# aqc-rev1.net
KiCad netlist of a schematic drawn in EAGLE
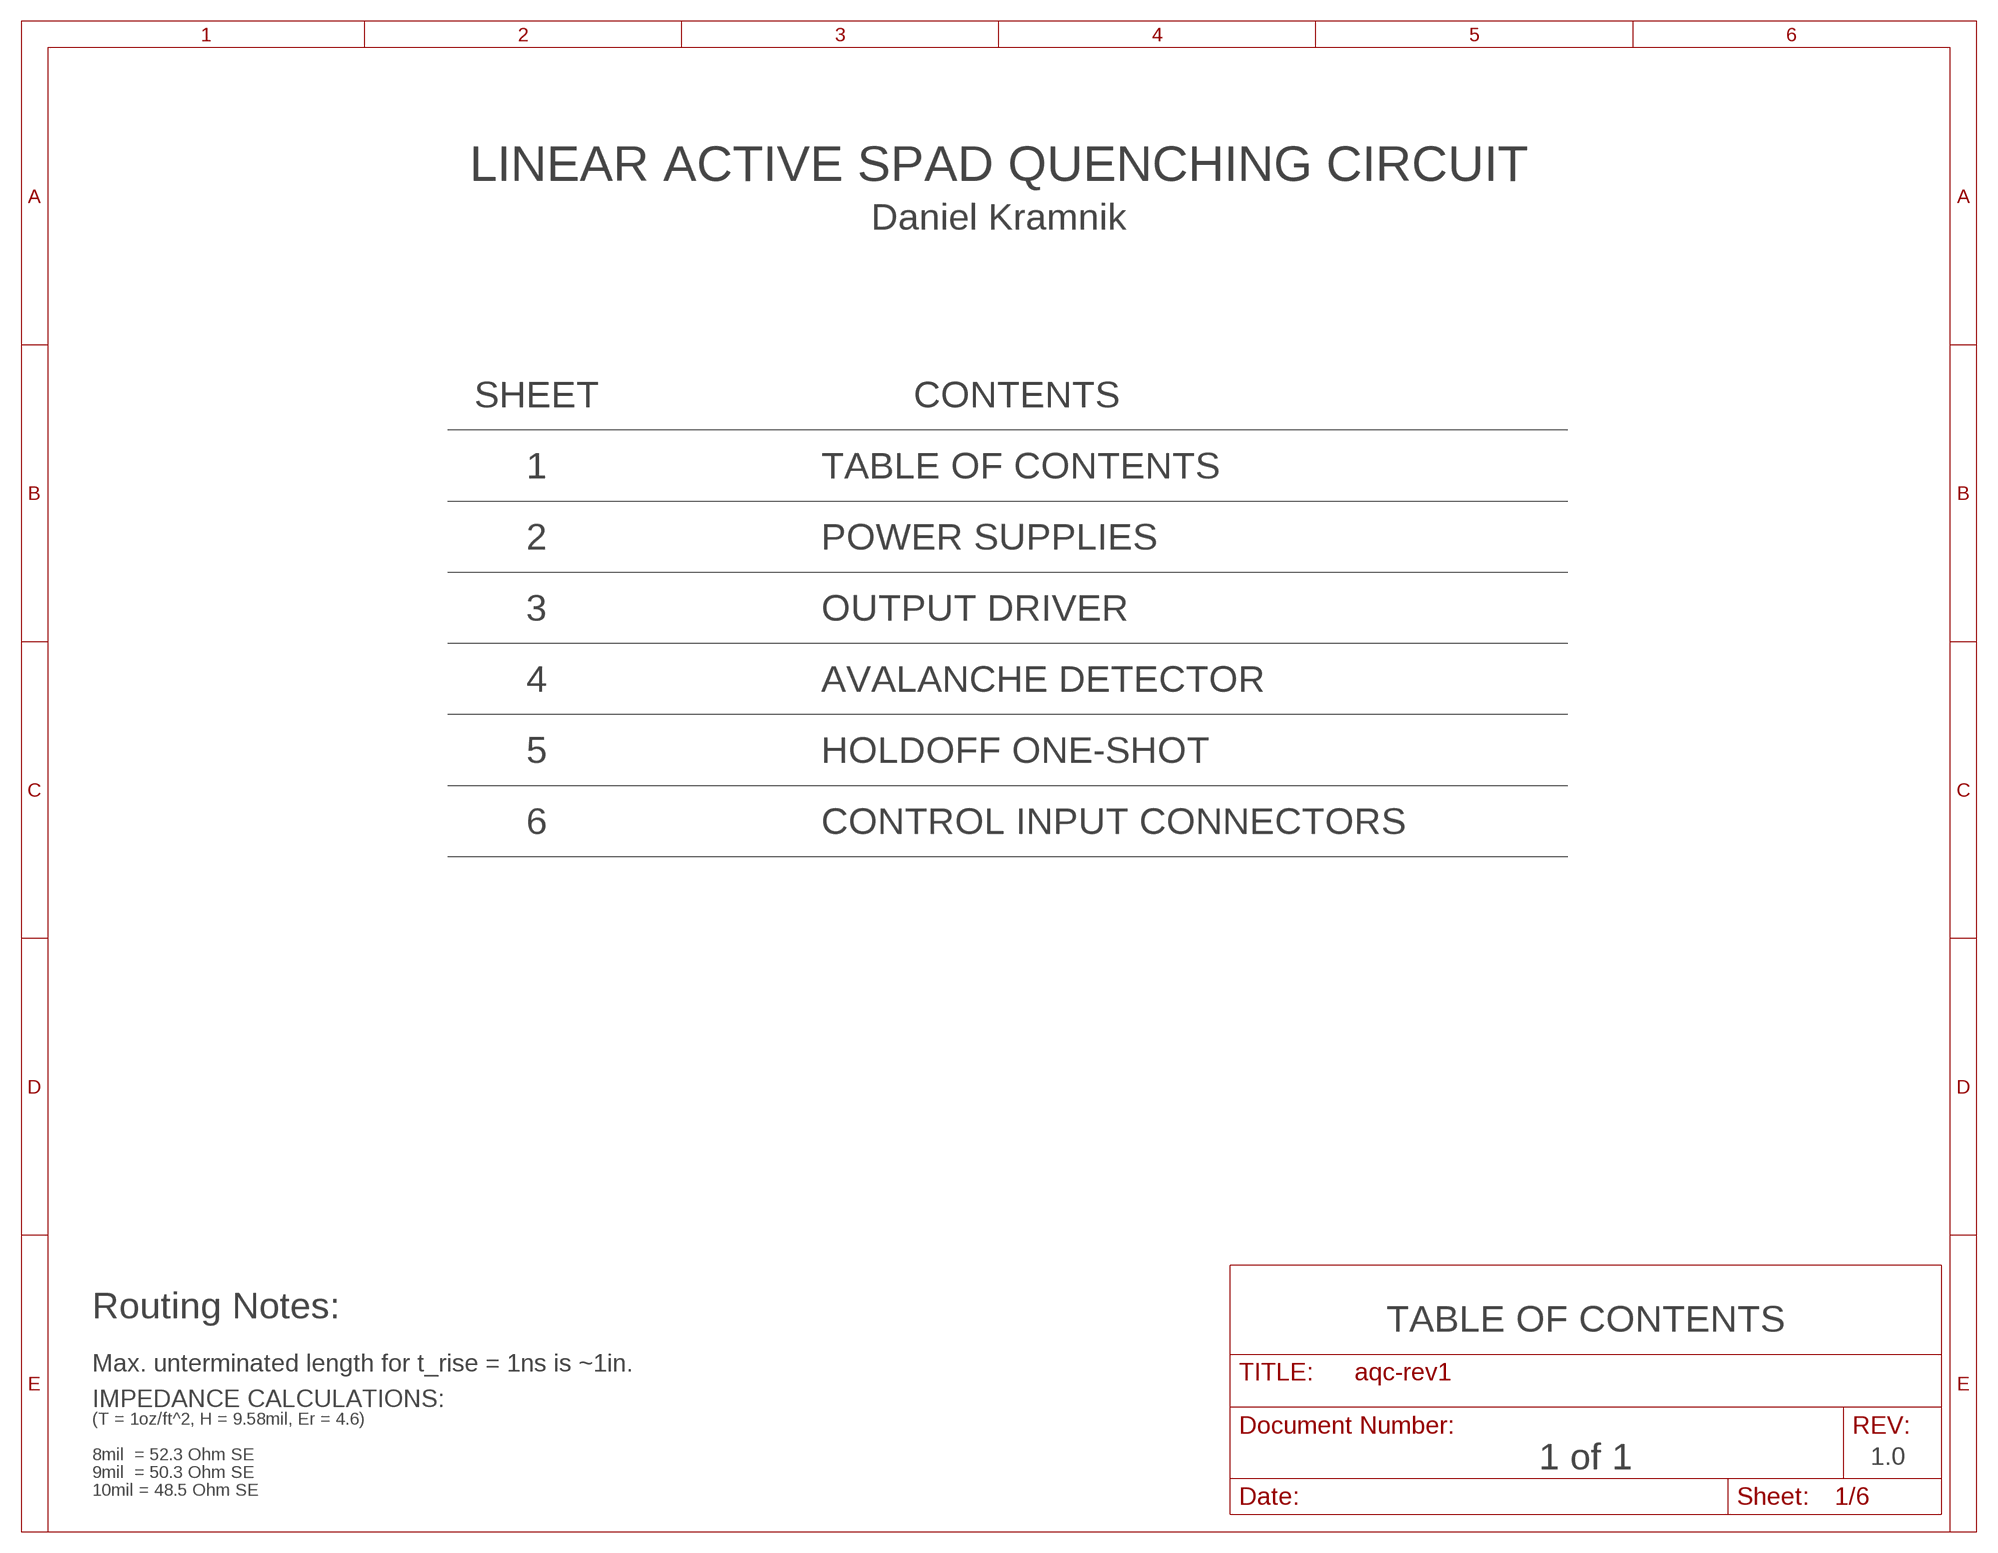
[diagram p0: schematic, sheet 1]
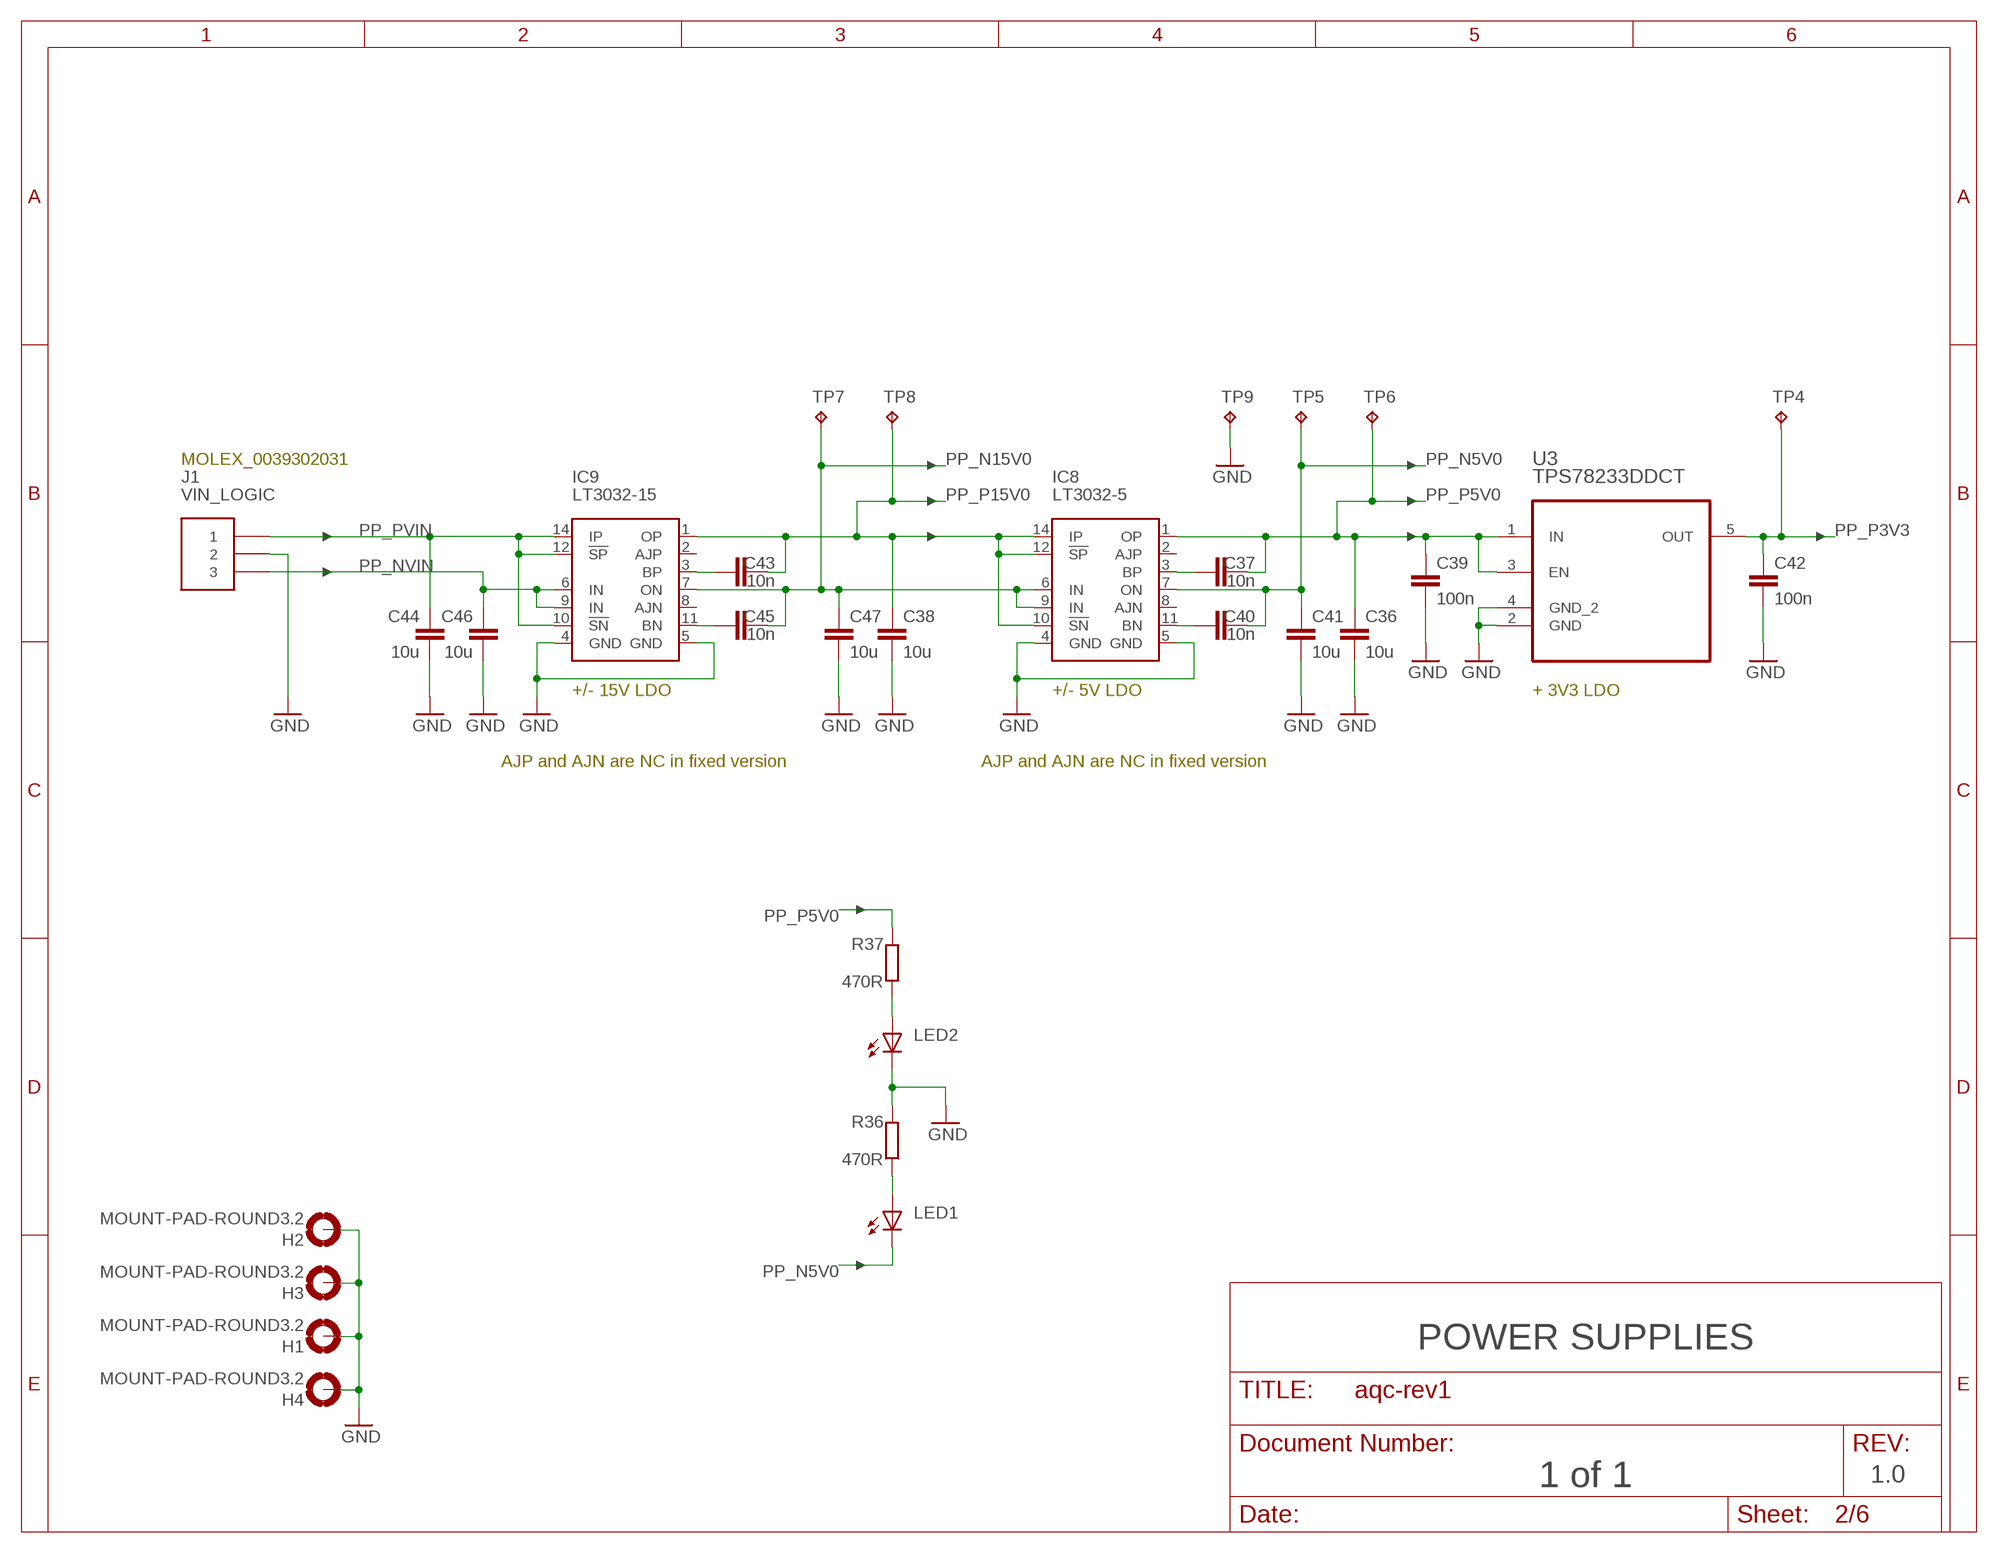
[diagram p1: schematic, sheet 2]
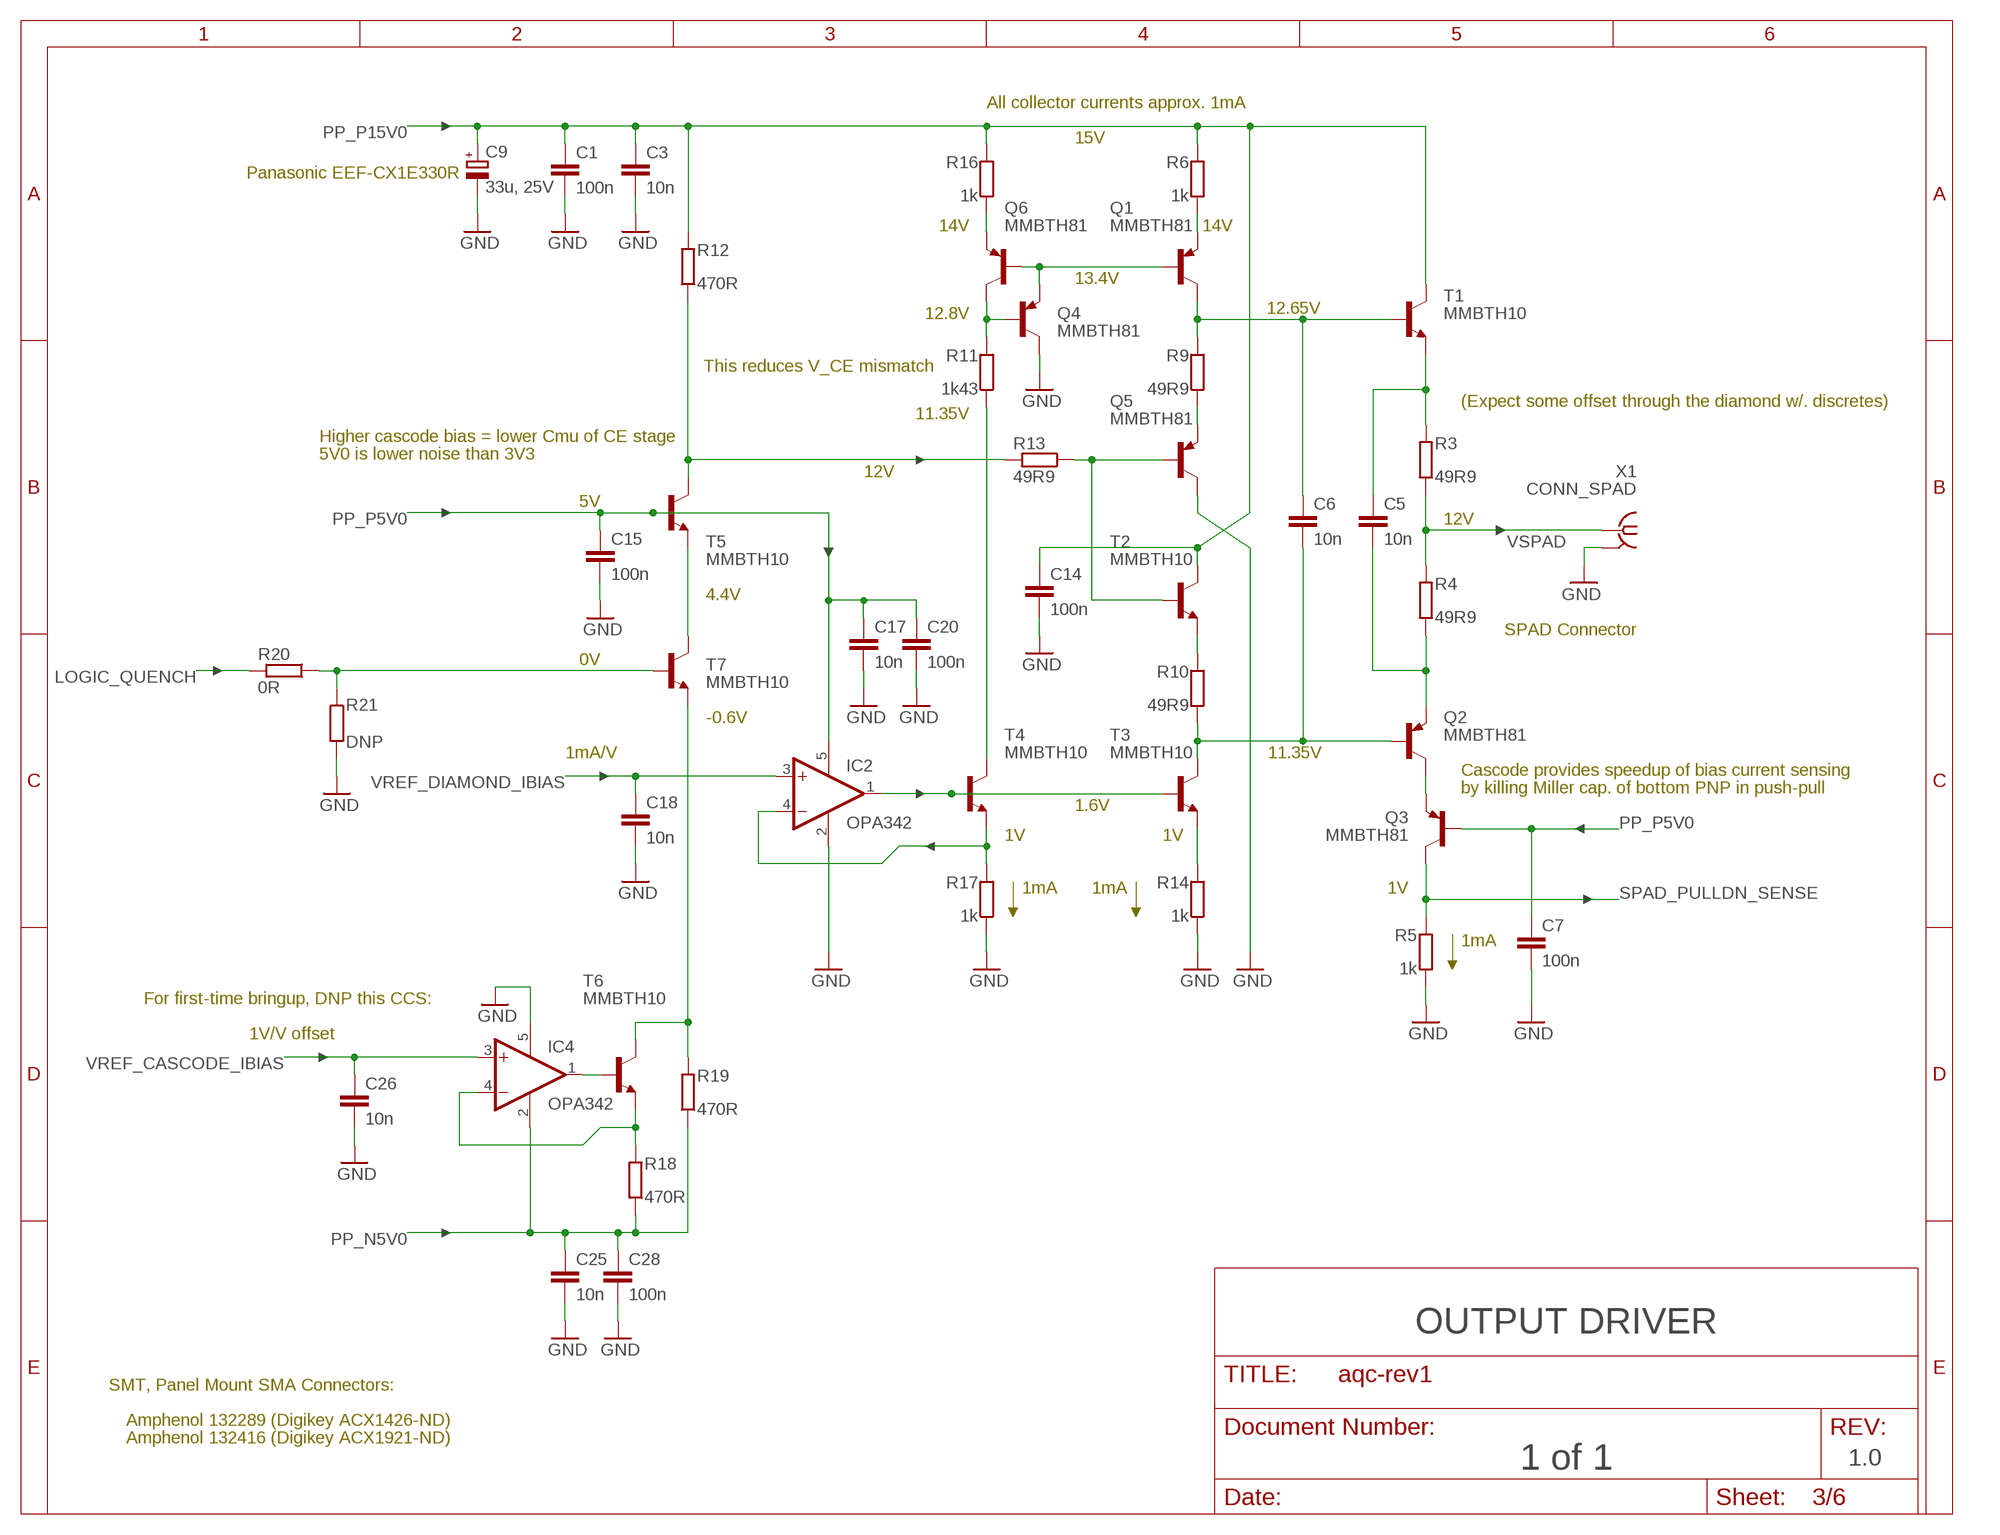
[diagram p2: schematic, sheet 3]
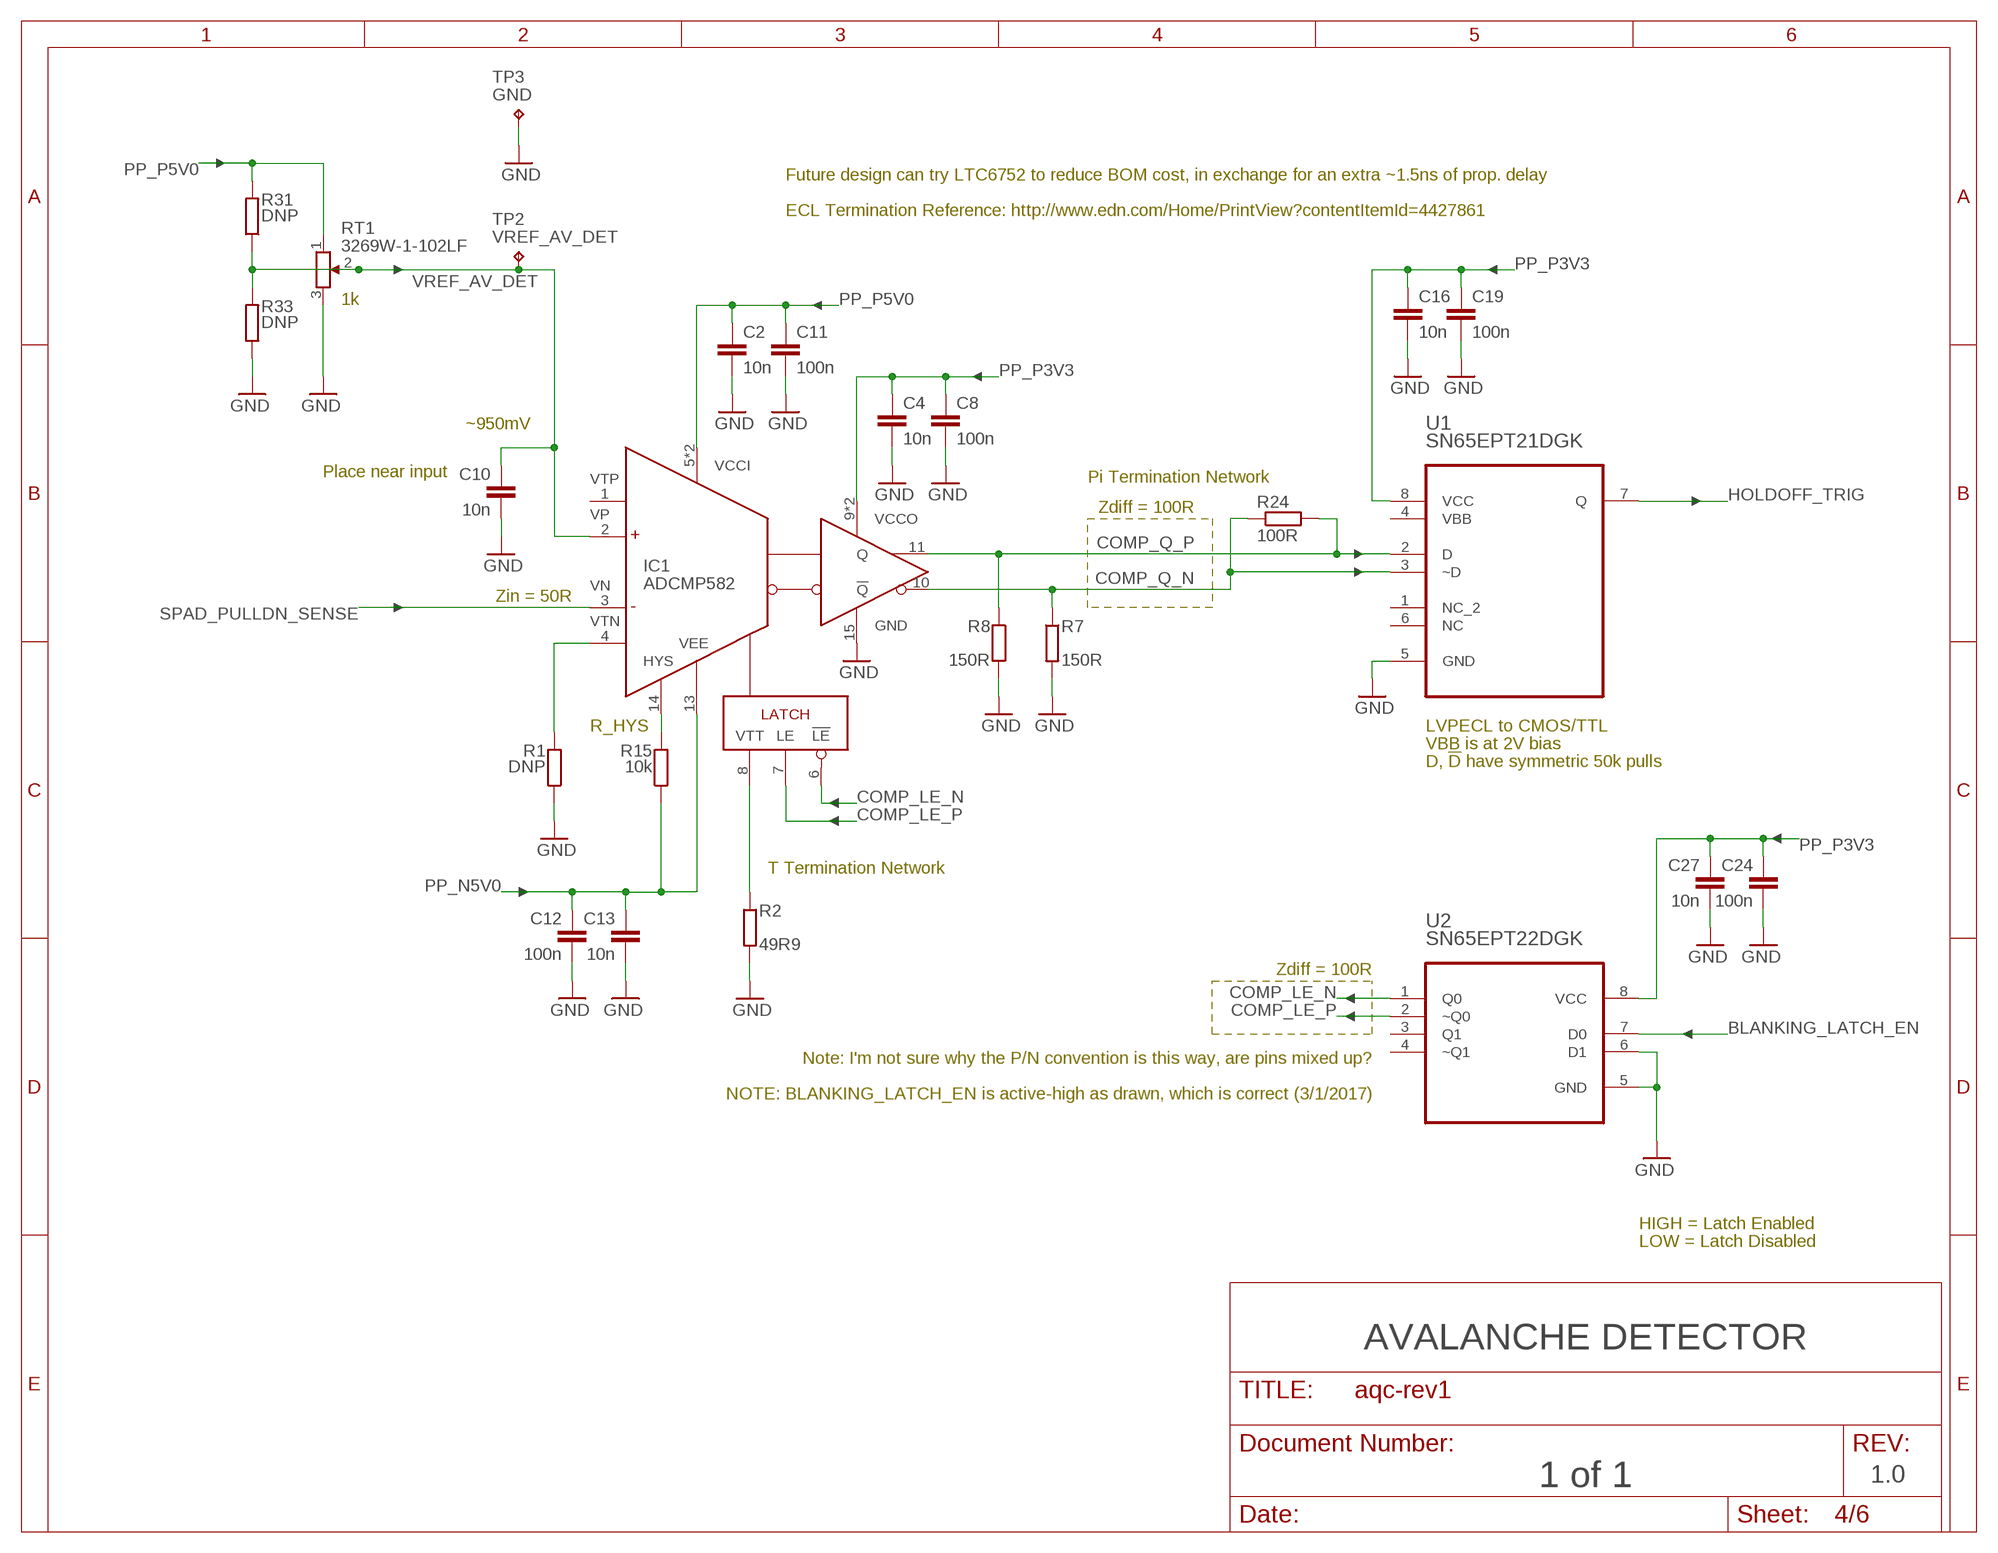
[diagram p3: schematic, sheet 4]
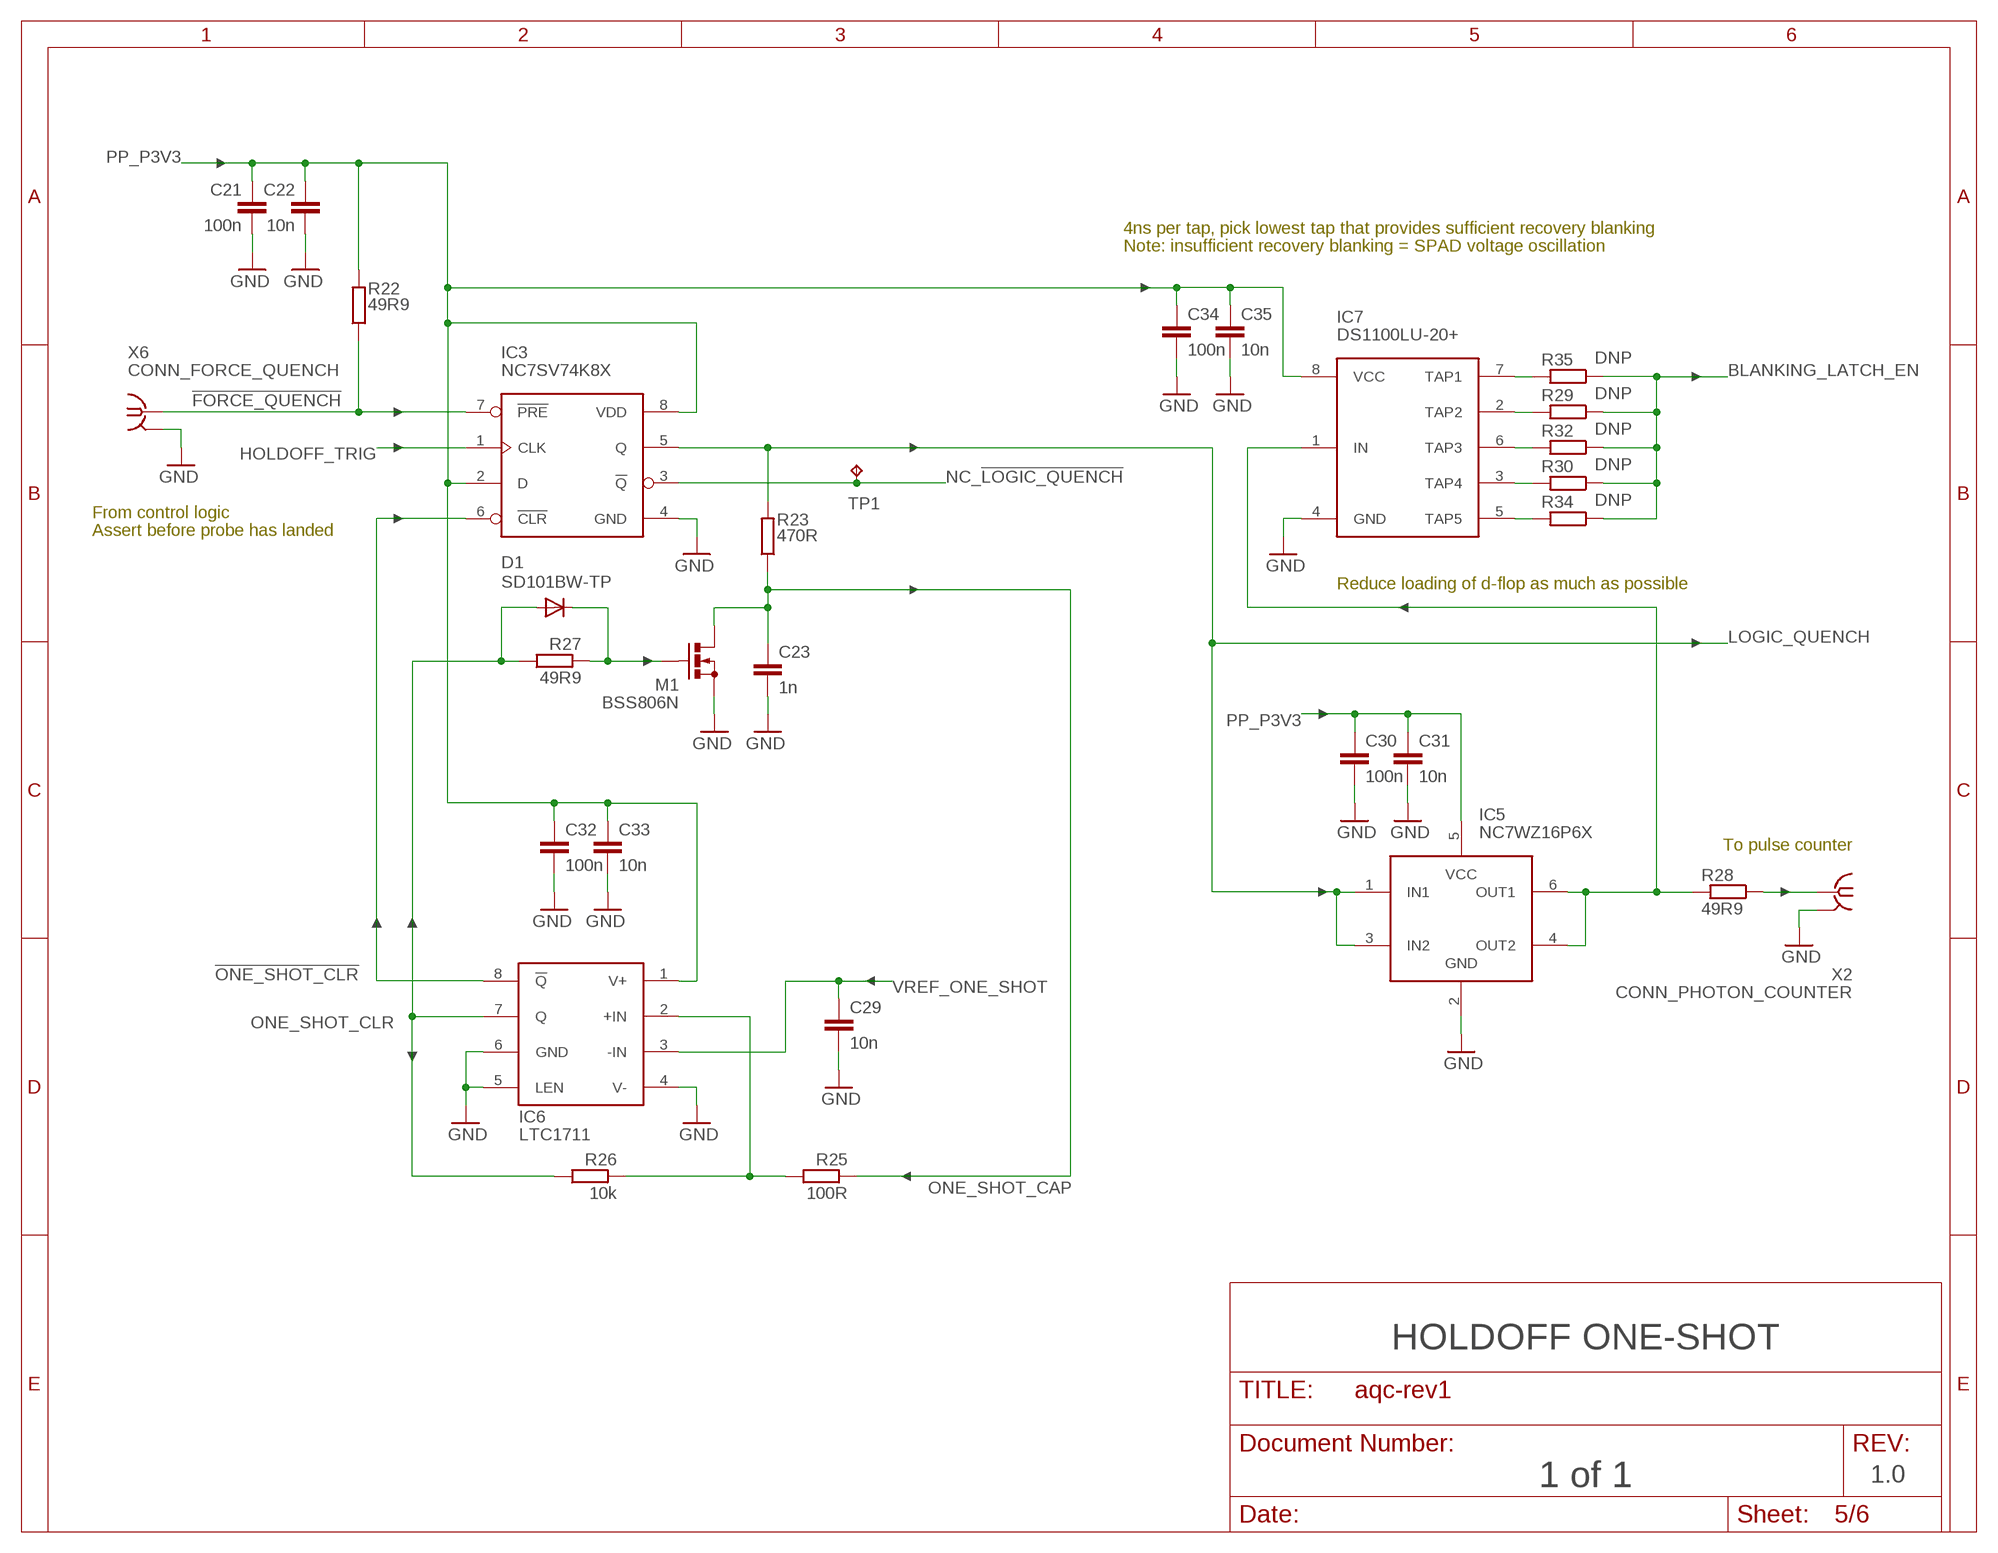
[diagram p4: schematic, sheet 5]
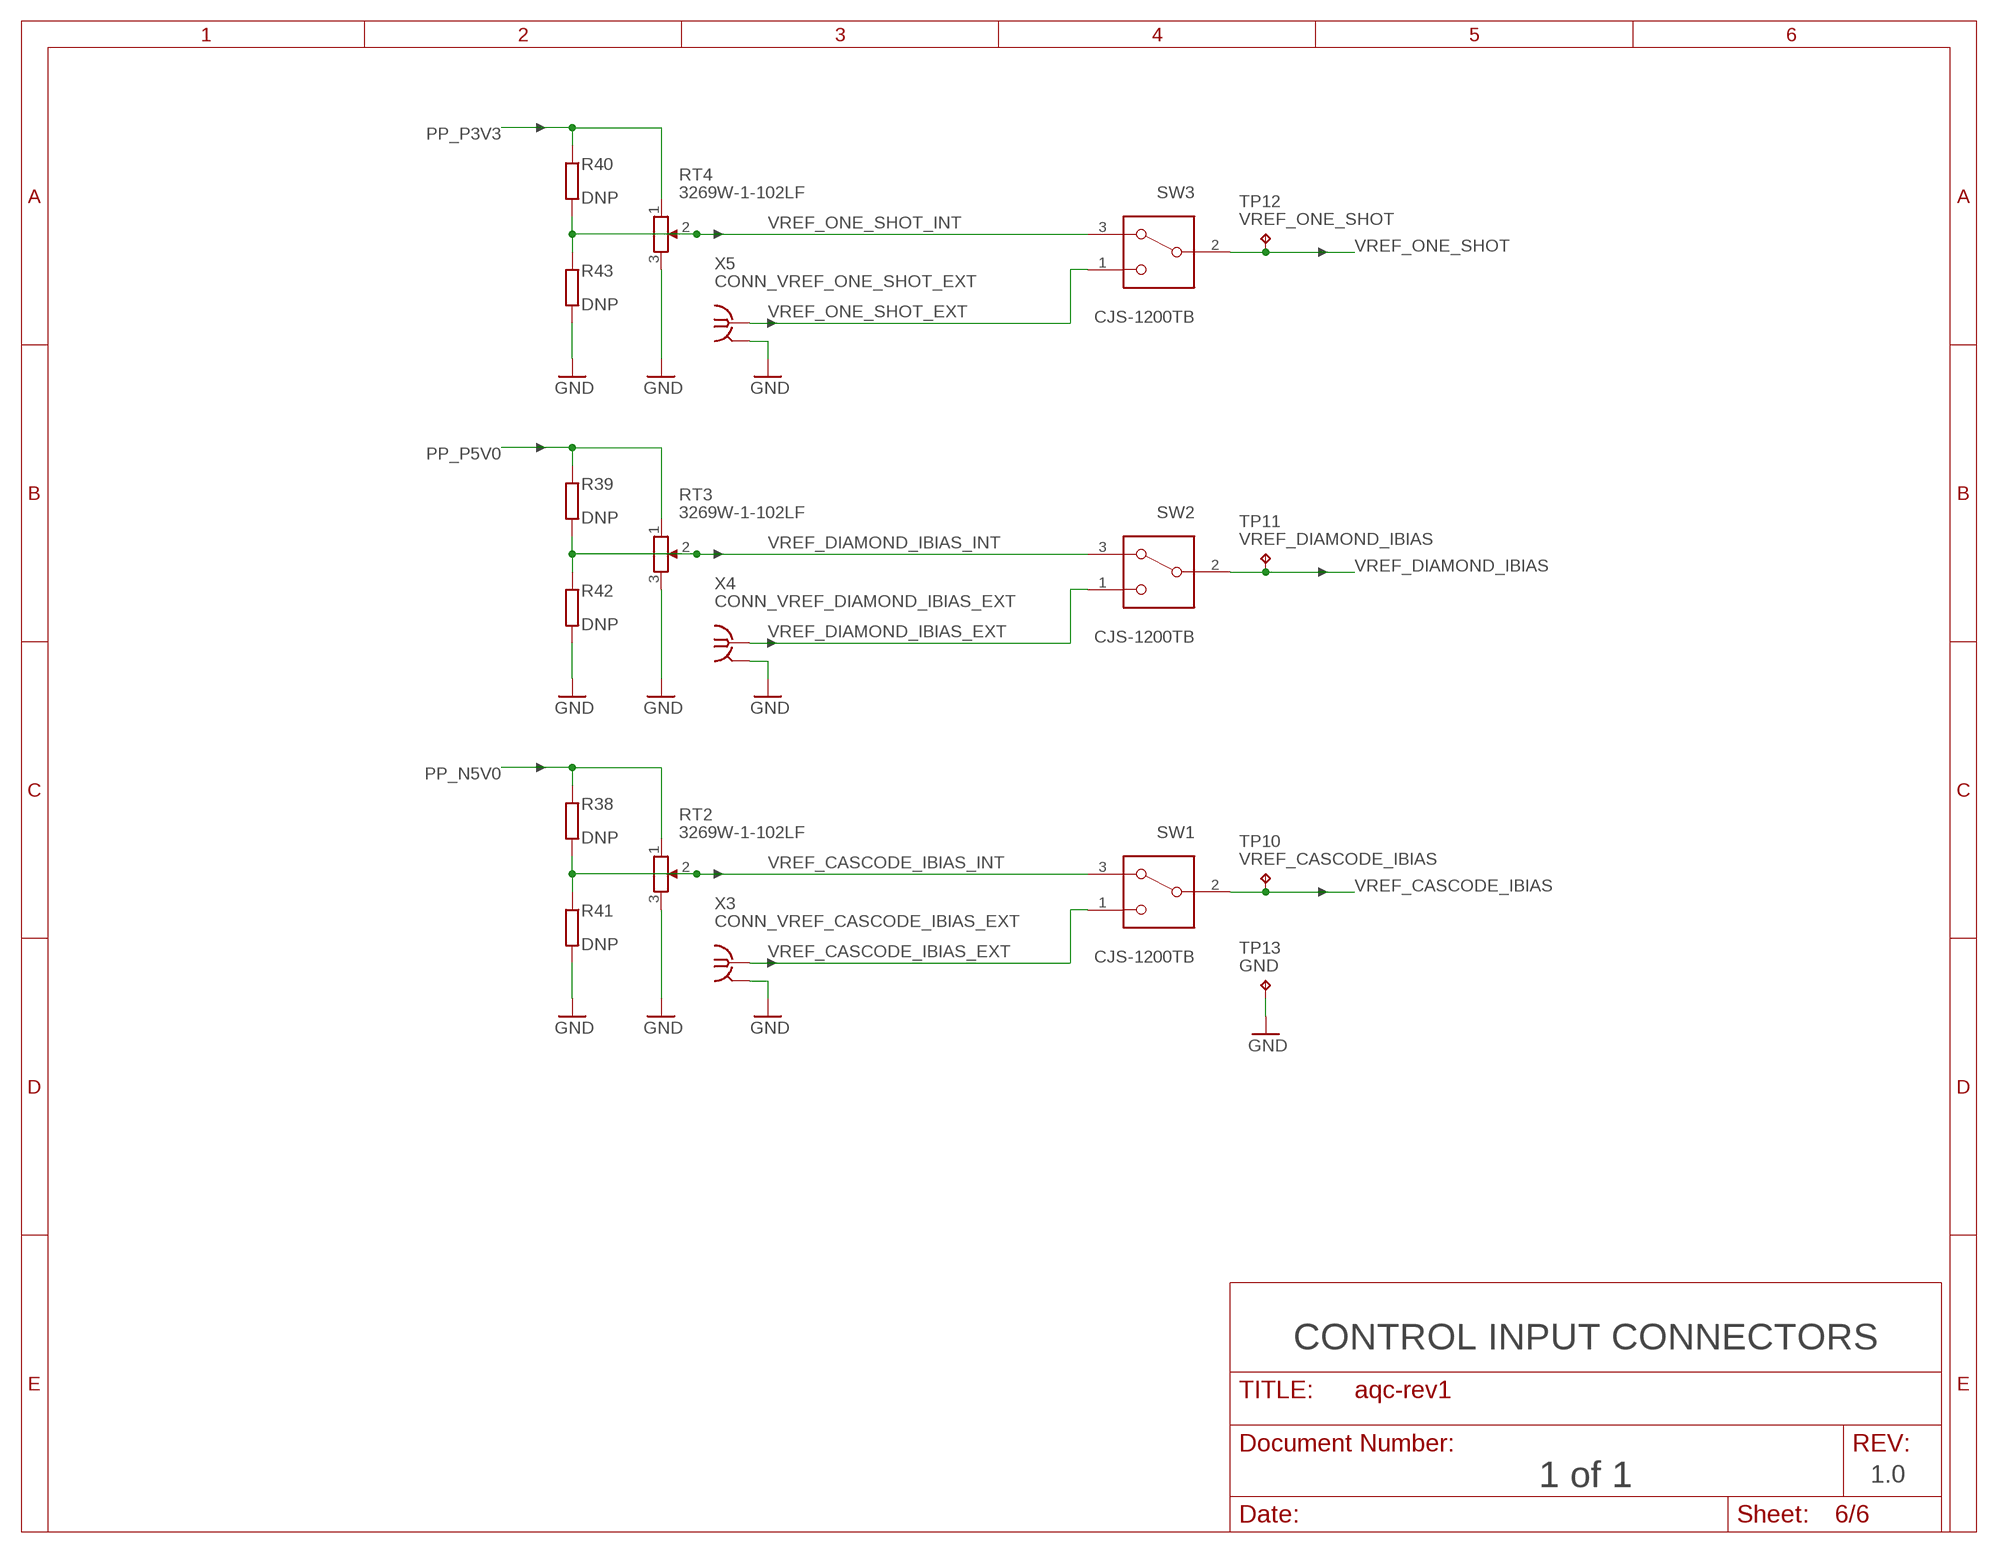
[diagram p5: schematic, sheet 6]

(export (version "E")
  (design (tool "Eeschema 10.0.6"))
  (components
    (comp (ref "C2")
      (value "10n")
      (footprint "eagle-import:C0402")
      (libsource (lib "eagle-import") (part "C-EUC0402"))
    )
    (comp (ref "C4")
      (value "10n")
      (footprint "eagle-import:C0402")
      (libsource (lib "eagle-import") (part "C-EUC0402"))
    )
    (comp (ref "C8")
      (value "100n")
      (footprint "eagle-import:C0402")
      (libsource (lib "eagle-import") (part "C-EUC0402"))
    )
    (comp (ref "C10")
      (value "10n")
      (footprint "eagle-import:C0603")
      (libsource (lib "eagle-import") (part "C-EUC0603"))
    )
    (comp (ref "C11")
      (value "100n")
      (footprint "eagle-import:C0402")
      (libsource (lib "eagle-import") (part "C-EUC0402"))
    )
    (comp (ref "C12")
      (value "100n")
      (footprint "eagle-import:C0402")
      (libsource (lib "eagle-import") (part "C-EUC0402"))
    )
    (comp (ref "C13")
      (value "10n")
      (footprint "eagle-import:C0402")
      (libsource (lib "eagle-import") (part "C-EUC0402"))
    )
    (comp (ref "C16")
      (value "10n")
      (footprint "eagle-import:C0402")
      (libsource (lib "eagle-import") (part "C-EUC0402"))
    )
    (comp (ref "C19")
      (value "100n")
      (footprint "eagle-import:C0402")
      (libsource (lib "eagle-import") (part "C-EUC0402"))
    )
    (comp (ref "C24")
      (value "100n")
      (footprint "eagle-import:C0402")
      (libsource (lib "eagle-import") (part "C-EUC0402"))
    )
    (comp (ref "C27")
      (value "10n")
      (footprint "eagle-import:C0402")
      (libsource (lib "eagle-import") (part "C-EUC0402"))
    )
    (comp (ref "IC1")
      (value "ADCMP582")
      (footprint "eagle-import:QFN50P300X300X80-16N")
      (libsource (lib "eagle-import") (part "ADCMP582"))
    )
    (comp (ref "R1")
      (value "DNP")
      (footprint "eagle-import:R0603")
      (libsource (lib "eagle-import") (part "R-EU_R0603"))
    )
    (comp (ref "R2")
      (value "49R9")
      (footprint "eagle-import:R0603")
      (libsource (lib "eagle-import") (part "R-EU_R0603"))
    )
    (comp (ref "R7")
      (value "150R")
      (footprint "eagle-import:R0402")
      (libsource (lib "eagle-import") (part "R-EU_R0402"))
    )
    (comp (ref "R8")
      (value "150R")
      (footprint "eagle-import:R0402")
      (libsource (lib "eagle-import") (part "R-EU_R0402"))
    )
    (comp (ref "R15")
      (value "10k")
      (footprint "eagle-import:R0603")
      (libsource (lib "eagle-import") (part "R-EU_R0603"))
    )
    (comp (ref "R24")
      (value "100R")
      (footprint "eagle-import:R0402")
      (libsource (lib "eagle-import") (part "R-EU_R0402"))
    )
    (comp (ref "R31")
      (value "DNP")
      (footprint "eagle-import:R0603")
      (libsource (lib "eagle-import") (part "R-EU_R0603"))
    )
    (comp (ref "R33")
      (value "DNP")
      (footprint "eagle-import:R0603")
      (libsource (lib "eagle-import") (part "R-EU_R0603"))
    )
    (comp (ref "RT1")
      (value "3269W-1-102LF")
      (footprint "eagle-import:3269W")
      (libsource (lib "eagle-import") (part "BOURNS_3269WX"))
    )
    (comp (ref "TP2")
      (value "VREF_AV_DET")
      (footprint "eagle-import:KEYSTONE_5000_MINIATURE")
      (libsource (lib "eagle-import") (part "KEYSTONE_5000"))
    )
    (comp (ref "TP3")
      (value "GND")
      (footprint "eagle-import:KEYSTONE_5000_MINIATURE")
      (libsource (lib "eagle-import") (part "KEYSTONE_5000"))
    )
    (comp (ref "U1")
      (value "SN65EPT21DGK")
      (footprint "eagle-import:SOP65P490X110-8N")
      (libsource (lib "eagle-import") (part "SN65EPT21DGK"))
    )
    (comp (ref "U2")
      (value "SN65EPT22DGK")
      (footprint "eagle-import:SOP65P490X110-8N")
      (libsource (lib "eagle-import") (part "SN65EPT22DGK"))
    )
    (comp (ref "C36")
      (value "10u")
      (footprint "eagle-import:C1206")
      (libsource (lib "eagle-import") (part "C-EUC1206"))
    )
    (comp (ref "C37")
      (value "10n")
      (footprint "eagle-import:C0603")
      (libsource (lib "eagle-import") (part "C-EUC0603"))
    )
    (comp (ref "C38")
      (value "10u")
      (footprint "eagle-import:C1206")
      (libsource (lib "eagle-import") (part "C-EUC1206"))
    )
    (comp (ref "C39")
      (value "100n")
      (footprint "eagle-import:C0603")
      (libsource (lib "eagle-import") (part "C-EUC0603"))
    )
    (comp (ref "C40")
      (value "10n")
      (footprint "eagle-import:C0603")
      (libsource (lib "eagle-import") (part "C-EUC0603"))
    )
    (comp (ref "C41")
      (value "10u")
      (footprint "eagle-import:C1206")
      (libsource (lib "eagle-import") (part "C-EUC1206"))
    )
    (comp (ref "C42")
      (value "100n")
      (footprint "eagle-import:C0603")
      (libsource (lib "eagle-import") (part "C-EUC0603"))
    )
    (comp (ref "C43")
      (value "10n")
      (footprint "eagle-import:C0603")
      (libsource (lib "eagle-import") (part "C-EUC0603"))
    )
    (comp (ref "C44")
      (value "10u")
      (footprint "eagle-import:C1206")
      (libsource (lib "eagle-import") (part "C-EUC1206"))
    )
    (comp (ref "C45")
      (value "10n")
      (footprint "eagle-import:C0603")
      (libsource (lib "eagle-import") (part "C-EUC0603"))
    )
    (comp (ref "C46")
      (value "10u")
      (footprint "eagle-import:C1206")
      (libsource (lib "eagle-import") (part "C-EUC1206"))
    )
    (comp (ref "C47")
      (value "10u")
      (footprint "eagle-import:C1206")
      (libsource (lib "eagle-import") (part "C-EUC1206"))
    )
    (comp (ref "H1")
      (value "MOUNT-PAD-ROUND3.2")
      (footprint "eagle-import:3,2-PAD")
      (libsource (lib "eagle-import") (part "MOUNT-PAD-ROUND3.2"))
    )
    (comp (ref "H2")
      (value "MOUNT-PAD-ROUND3.2")
      (footprint "eagle-import:3,2-PAD")
      (libsource (lib "eagle-import") (part "MOUNT-PAD-ROUND3.2"))
    )
    (comp (ref "H3")
      (value "MOUNT-PAD-ROUND3.2")
      (footprint "eagle-import:3,2-PAD")
      (libsource (lib "eagle-import") (part "MOUNT-PAD-ROUND3.2"))
    )
    (comp (ref "H4")
      (value "MOUNT-PAD-ROUND3.2")
      (footprint "eagle-import:3,2-PAD")
      (libsource (lib "eagle-import") (part "MOUNT-PAD-ROUND3.2"))
    )
    (comp (ref "IC8")
      (value "LT3032-5")
      (footprint "eagle-import:DFN14-4X3DE")
      (libsource (lib "eagle-import") (part "LT3032"))
    )
    (comp (ref "IC9")
      (value "LT3032-15")
      (footprint "eagle-import:DFN14-4X3DE")
      (libsource (lib "eagle-import") (part "LT3032"))
    )
    (comp (ref "J1")
      (value "VIN_LOGIC")
      (footprint "eagle-import:CONN_MOLEX_3PIN_MINI-FIT_JR")
      (libsource (lib "eagle-import") (part "CONN_MOLEX_3PIN_MINI-FIT_JR"))
    )
    (comp (ref "LED1")
      (value "LEDCHIP-LED0805")
      (footprint "eagle-import:CHIP-LED0805")
      (libsource (lib "eagle-import") (part "LEDCHIP-LED0805"))
    )
    (comp (ref "LED2")
      (value "LEDCHIP-LED0805")
      (footprint "eagle-import:CHIP-LED0805")
      (libsource (lib "eagle-import") (part "LEDCHIP-LED0805"))
    )
    (comp (ref "R36")
      (value "470R")
      (footprint "eagle-import:R0805")
      (libsource (lib "eagle-import") (part "resistor_R-EU_R0805"))
    )
    (comp (ref "R37")
      (value "470R")
      (footprint "eagle-import:R0805")
      (libsource (lib "eagle-import") (part "resistor_R-EU_R0805"))
    )
    (comp (ref "TP4")
      (value "TPTP20R")
      (footprint "eagle-import:TP20R")
      (libsource (lib "eagle-import") (part "TPTP20R"))
    )
    (comp (ref "TP5")
      (value "TPTP20R")
      (footprint "eagle-import:TP20R")
      (libsource (lib "eagle-import") (part "TPTP20R"))
    )
    (comp (ref "TP6")
      (value "TPTP20R")
      (footprint "eagle-import:TP20R")
      (libsource (lib "eagle-import") (part "TPTP20R"))
    )
    (comp (ref "TP7")
      (value "TPTP20R")
      (footprint "eagle-import:TP20R")
      (libsource (lib "eagle-import") (part "TPTP20R"))
    )
    (comp (ref "TP8")
      (value "TPTP20R")
      (footprint "eagle-import:TP20R")
      (libsource (lib "eagle-import") (part "TPTP20R"))
    )
    (comp (ref "TP9")
      (value "TPTP20R")
      (footprint "eagle-import:TP20R")
      (libsource (lib "eagle-import") (part "TPTP20R"))
    )
    (comp (ref "U3")
      (value "TPS78233DDCT")
      (footprint "eagle-import:SOT95P280X110-5N")
      (libsource (lib "eagle-import") (part "TPS78233DDCT"))
    )
    (comp (ref "C1")
      (value "100n")
      (footprint "eagle-import:C0603")
      (libsource (lib "eagle-import") (part "C-EUC0603"))
    )
    (comp (ref "C3")
      (value "10n")
      (footprint "eagle-import:C0603")
      (libsource (lib "eagle-import") (part "C-EUC0603"))
    )
    (comp (ref "C5")
      (value "10n")
      (footprint "eagle-import:C0603")
      (libsource (lib "eagle-import") (part "C-EUC0603"))
    )
    (comp (ref "C6")
      (value "10n")
      (footprint "eagle-import:C0603")
      (libsource (lib "eagle-import") (part "C-EUC0603"))
    )
    (comp (ref "C7")
      (value "100n")
      (footprint "eagle-import:C0603")
      (libsource (lib "eagle-import") (part "C-EUC0603"))
    )
    (comp (ref "C9")
      (value "33u, 25V")
      (footprint "eagle-import:CT7343")
      (libsource (lib "eagle-import") (part "CPOL-EUCT7343"))
    )
    (comp (ref "C14")
      (value "100n")
      (footprint "eagle-import:C0603")
      (libsource (lib "eagle-import") (part "C-EUC0603"))
    )
    (comp (ref "C15")
      (value "100n")
      (footprint "eagle-import:C0603")
      (libsource (lib "eagle-import") (part "C-EUC0603"))
    )
    (comp (ref "C17")
      (value "10n")
      (footprint "eagle-import:C0402")
      (libsource (lib "eagle-import") (part "C-EUC0402"))
    )
    (comp (ref "C18")
      (value "10n")
      (footprint "eagle-import:C0402")
      (libsource (lib "eagle-import") (part "C-EUC0402"))
    )
    (comp (ref "C20")
      (value "100n")
      (footprint "eagle-import:C0402")
      (libsource (lib "eagle-import") (part "C-EUC0402"))
    )
    (comp (ref "C25")
      (value "10n")
      (footprint "eagle-import:C0402")
      (libsource (lib "eagle-import") (part "C-EUC0402"))
    )
    (comp (ref "C26")
      (value "10n")
      (footprint "eagle-import:C0402")
      (libsource (lib "eagle-import") (part "C-EUC0402"))
    )
    (comp (ref "C28")
      (value "100n")
      (footprint "eagle-import:C0402")
      (libsource (lib "eagle-import") (part "C-EUC0402"))
    )
    (comp (ref "IC2")
      (value "OPA342")
      (footprint "eagle-import:SOT23-5")
      (libsource (lib "eagle-import") (part "OPA333DBV"))
    )
    (comp (ref "IC4")
      (value "OPA342")
      (footprint "eagle-import:SOT23-5")
      (libsource (lib "eagle-import") (part "OPA333DBV"))
    )
    (comp (ref "Q1")
      (value "MMBTH81")
      (footprint "eagle-import:SOT23-BEC")
      (libsource (lib "eagle-import") (part "MMBTH81SMDLT1"))
    )
    (comp (ref "Q2")
      (value "MMBTH81")
      (footprint "eagle-import:SOT23-BEC")
      (libsource (lib "eagle-import") (part "MMBTH81SMDLT1"))
    )
    (comp (ref "Q3")
      (value "MMBTH81")
      (footprint "eagle-import:SOT23-BEC")
      (libsource (lib "eagle-import") (part "MMBTH81SMDLT1"))
    )
    (comp (ref "Q4")
      (value "MMBTH81")
      (footprint "eagle-import:SOT23-BEC")
      (libsource (lib "eagle-import") (part "MMBTH81SMDLT1"))
    )
    (comp (ref "Q5")
      (value "MMBTH81")
      (footprint "eagle-import:SOT23-BEC")
      (libsource (lib "eagle-import") (part "MMBTH81SMDLT1"))
    )
    (comp (ref "Q6")
      (value "MMBTH81")
      (footprint "eagle-import:SOT23-BEC")
      (libsource (lib "eagle-import") (part "MMBTH81SMDLT1"))
    )
    (comp (ref "R3")
      (value "49R9")
      (footprint "eagle-import:R0603")
      (libsource (lib "eagle-import") (part "R-EU_R0603"))
    )
    (comp (ref "R4")
      (value "49R9")
      (footprint "eagle-import:R0603")
      (libsource (lib "eagle-import") (part "R-EU_R0603"))
    )
    (comp (ref "R5")
      (value "1k")
      (footprint "eagle-import:R0603")
      (libsource (lib "eagle-import") (part "R-EU_R0603"))
    )
    (comp (ref "R6")
      (value "1k")
      (footprint "eagle-import:R0603")
      (libsource (lib "eagle-import") (part "R-EU_R0603"))
    )
    (comp (ref "R9")
      (value "49R9")
      (footprint "eagle-import:R0603")
      (libsource (lib "eagle-import") (part "R-EU_R0603"))
    )
    (comp (ref "R10")
      (value "49R9")
      (footprint "eagle-import:R0603")
      (libsource (lib "eagle-import") (part "R-EU_R0603"))
    )
    (comp (ref "R11")
      (value "1k43")
      (footprint "eagle-import:R0603")
      (libsource (lib "eagle-import") (part "R-EU_R0603"))
    )
    (comp (ref "R12")
      (value "470R")
      (footprint "eagle-import:R0603")
      (libsource (lib "eagle-import") (part "R-EU_R0603"))
    )
    (comp (ref "R13")
      (value "49R9")
      (footprint "eagle-import:R0603")
      (libsource (lib "eagle-import") (part "R-EU_R0603"))
    )
    (comp (ref "R14")
      (value "1k")
      (footprint "eagle-import:R0603")
      (libsource (lib "eagle-import") (part "R-EU_R0603"))
    )
    (comp (ref "R16")
      (value "1k")
      (footprint "eagle-import:R0603")
      (libsource (lib "eagle-import") (part "R-EU_R0603"))
    )
    (comp (ref "R17")
      (value "1k")
      (footprint "eagle-import:R0603")
      (libsource (lib "eagle-import") (part "R-EU_R0603"))
    )
    (comp (ref "R18")
      (value "470R")
      (footprint "eagle-import:R0603")
      (libsource (lib "eagle-import") (part "R-EU_R0603"))
    )
    (comp (ref "R19")
      (value "470R")
      (footprint "eagle-import:R0603")
      (libsource (lib "eagle-import") (part "R-EU_R0603"))
    )
    (comp (ref "R20")
      (value "0R")
      (footprint "eagle-import:R0603")
      (libsource (lib "eagle-import") (part "R-EU_R0603"))
    )
    (comp (ref "R21")
      (value "DNP")
      (footprint "eagle-import:R0603")
      (libsource (lib "eagle-import") (part "R-EU_R0603"))
    )
    (comp (ref "T1")
      (value "MMBTH10")
      (footprint "eagle-import:SOT23-BEC")
      (libsource (lib "eagle-import") (part "-NPN-SOT23-BECMMBTH10LT1"))
    )
    (comp (ref "T2")
      (value "MMBTH10")
      (footprint "eagle-import:SOT23-BEC")
      (libsource (lib "eagle-import") (part "-NPN-SOT23-BECMMBTH10LT1"))
    )
    (comp (ref "T3")
      (value "MMBTH10")
      (footprint "eagle-import:SOT23-BEC")
      (libsource (lib "eagle-import") (part "-NPN-SOT23-BECMMBTH10LT1"))
    )
    (comp (ref "T4")
      (value "MMBTH10")
      (footprint "eagle-import:SOT23-BEC")
      (libsource (lib "eagle-import") (part "-NPN-SOT23-BECMMBTH10LT1"))
    )
    (comp (ref "T5")
      (value "MMBTH10")
      (footprint "eagle-import:SOT23-BEC")
      (libsource (lib "eagle-import") (part "-NPN-SOT23-BECMMBTH10LT1"))
    )
    (comp (ref "T6")
      (value "MMBTH10")
      (footprint "eagle-import:SOT23-BEC")
      (libsource (lib "eagle-import") (part "-NPN-SOT23-BECMMBTH10LT1"))
    )
    (comp (ref "T7")
      (value "MMBTH10")
      (footprint "eagle-import:SOT23-BEC")
      (libsource (lib "eagle-import") (part "-NPN-SOT23-BECMMBTH10LT1"))
    )
    (comp (ref "X1")
      (value "CONN_SPAD")
      (footprint "eagle-import:J502-ND-142-0711-871_876")
      (fields (field (name "MF") "JOHNSON COMPONENTS") (field (name "MPN") "142-0711-871"))
      (libsource (lib "eagle-import") (part "SMA-142-0711-871/876"))
    )
    (comp (ref "C21")
      (value "100n")
      (footprint "eagle-import:C0402")
      (libsource (lib "eagle-import") (part "C-EUC0402"))
    )
    (comp (ref "C22")
      (value "10n")
      (footprint "eagle-import:C0402")
      (libsource (lib "eagle-import") (part "C-EUC0402"))
    )
    (comp (ref "C23")
      (value "1n")
      (footprint "eagle-import:C0603")
      (libsource (lib "eagle-import") (part "C-EUC0603"))
    )
    (comp (ref "C29")
      (value "10n")
      (footprint "eagle-import:C0402")
      (libsource (lib "eagle-import") (part "C-EUC0402"))
    )
    (comp (ref "C30")
      (value "100n")
      (footprint "eagle-import:C0402")
      (libsource (lib "eagle-import") (part "C-EUC0402"))
    )
    (comp (ref "C31")
      (value "10n")
      (footprint "eagle-import:C0402")
      (libsource (lib "eagle-import") (part "C-EUC0402"))
    )
    (comp (ref "C32")
      (value "100n")
      (footprint "eagle-import:C0402")
      (libsource (lib "eagle-import") (part "C-EUC0402"))
    )
    (comp (ref "C33")
      (value "10n")
      (footprint "eagle-import:C0402")
      (libsource (lib "eagle-import") (part "C-EUC0402"))
    )
    (comp (ref "C34")
      (value "100n")
      (footprint "eagle-import:C0402")
      (libsource (lib "eagle-import") (part "C-EUC0402"))
    )
    (comp (ref "C35")
      (value "10n")
      (footprint "eagle-import:C0402")
      (libsource (lib "eagle-import") (part "C-EUC0402"))
    )
    (comp (ref "D1")
      (value "SD101BW-TP")
      (footprint "eagle-import:SOD123")
      (libsource (lib "eagle-import") (part "DIODE-SOD123"))
    )
    (comp (ref "IC3")
      (value "NC7SV74K8X")
      (footprint "eagle-import:US8_3.1MM_JDEC_MO-187")
      (libsource (lib "eagle-import") (part "NC7SV74K8X"))
    )
    (comp (ref "IC5")
      (value "NC7WZ16P6X")
      (footprint "eagle-import:SC70-6L")
      (libsource (lib "eagle-import") (part "NC7WZ16P6X"))
    )
    (comp (ref "IC6")
      (value "LTC1711")
      (footprint "eagle-import:MSOP8")
      (libsource (lib "eagle-import") (part "LTC1711"))
    )
    (comp (ref "IC7")
      (value "DS1100LU-20+")
      (footprint "eagle-import:MSOP8")
      (libsource (lib "eagle-import") (part "DS1100L"))
    )
    (comp (ref "M1")
      (value "BSS806N")
      (footprint "eagle-import:SOT23R_INFINEON")
      (libsource (lib "eagle-import") (part "BSS806N"))
    )
    (comp (ref "R22")
      (value "49R9")
      (footprint "eagle-import:R0603")
      (libsource (lib "eagle-import") (part "R-EU_R0603"))
    )
    (comp (ref "R23")
      (value "470R")
      (footprint "eagle-import:R0603")
      (libsource (lib "eagle-import") (part "R-EU_R0603"))
    )
    (comp (ref "R25")
      (value "100R")
      (footprint "eagle-import:R0603")
      (libsource (lib "eagle-import") (part "R-EU_R0603"))
    )
    (comp (ref "R26")
      (value "10k")
      (footprint "eagle-import:R0603")
      (libsource (lib "eagle-import") (part "R-EU_R0603"))
    )
    (comp (ref "R27")
      (value "49R9")
      (footprint "eagle-import:R0603")
      (libsource (lib "eagle-import") (part "R-EU_R0603"))
    )
    (comp (ref "R28")
      (value "49R9")
      (footprint "eagle-import:R0603")
      (libsource (lib "eagle-import") (part "R-EU_R0603"))
    )
    (comp (ref "R29")
      (value "DNP")
      (footprint "eagle-import:R0603")
      (libsource (lib "eagle-import") (part "R-EU_R0603"))
    )
    (comp (ref "R30")
      (value "DNP")
      (footprint "eagle-import:R0603")
      (libsource (lib "eagle-import") (part "R-EU_R0603"))
    )
    (comp (ref "R32")
      (value "DNP")
      (footprint "eagle-import:R0603")
      (libsource (lib "eagle-import") (part "R-EU_R0603"))
    )
    (comp (ref "R34")
      (value "DNP")
      (footprint "eagle-import:R0603")
      (libsource (lib "eagle-import") (part "R-EU_R0603"))
    )
    (comp (ref "R35")
      (value "DNP")
      (footprint "eagle-import:R0603")
      (libsource (lib "eagle-import") (part "R-EU_R0603"))
    )
    (comp (ref "TP1")
      (value "TPTP08R")
      (footprint "eagle-import:TP08R")
      (libsource (lib "eagle-import") (part "TPTP08R"))
    )
    (comp (ref "X2")
      (value "CONN_PHOTON_COUNTER")
      (footprint "eagle-import:J502-ND-142-0711-871_876")
      (fields (field (name "MF") "JOHNSON COMPONENTS") (field (name "MPN") "142-0711-871"))
      (libsource (lib "eagle-import") (part "SMA-142-0711-871/876"))
    )
    (comp (ref "X6")
      (value "CONN_FORCE_QUENCH")
      (footprint "eagle-import:J502-ND-142-0711-871_876")
      (fields
        (field (name "MF") "JOHNSON COMPONENTS")
        (field (name "MPN") "142-0711-871")
        (field (name "MF_1") "JOHNSON COMPONENTS")
        (field (name "MPN_1") "142-0711-871")
        (field (name "OC_FARNELL") "unknown")
        (field (name "OC_NEWARK") "01C1639")
      )
      (libsource (lib "eagle-import") (part "SMA-142-0711-871/876"))
    )
    (comp (ref "R38")
      (value "DNP")
      (footprint "eagle-import:R0603")
      (libsource (lib "eagle-import") (part "R-EU_R0603"))
    )
    (comp (ref "R39")
      (value "DNP")
      (footprint "eagle-import:R0603")
      (libsource (lib "eagle-import") (part "R-EU_R0603"))
    )
    (comp (ref "R40")
      (value "DNP")
      (footprint "eagle-import:R0603")
      (libsource (lib "eagle-import") (part "R-EU_R0603"))
    )
    (comp (ref "R41")
      (value "DNP")
      (footprint "eagle-import:R0603")
      (libsource (lib "eagle-import") (part "R-EU_R0603"))
    )
    (comp (ref "R42")
      (value "DNP")
      (footprint "eagle-import:R0603")
      (libsource (lib "eagle-import") (part "R-EU_R0603"))
    )
    (comp (ref "R43")
      (value "DNP")
      (footprint "eagle-import:R0603")
      (libsource (lib "eagle-import") (part "R-EU_R0603"))
    )
    (comp (ref "RT2")
      (value "3269W-1-102LF")
      (footprint "eagle-import:3269W")
      (libsource (lib "eagle-import") (part "BOURNS_3269WX"))
    )
    (comp (ref "RT3")
      (value "3269W-1-102LF")
      (footprint "eagle-import:3269W")
      (libsource (lib "eagle-import") (part "BOURNS_3269WX"))
    )
    (comp (ref "RT4")
      (value "3269W-1-102LF")
      (footprint "eagle-import:3269W")
      (libsource (lib "eagle-import") (part "BOURNS_3269WX"))
    )
    (comp (ref "SW1")
      (value "CJS-1200TB")
      (footprint "eagle-import:CJS-1200TB")
      (libsource (lib "eagle-import") (part "CJS-1200TB"))
    )
    (comp (ref "SW2")
      (value "CJS-1200TB")
      (footprint "eagle-import:CJS-1200TB")
      (libsource (lib "eagle-import") (part "CJS-1200TB"))
    )
    (comp (ref "SW3")
      (value "CJS-1200TB")
      (footprint "eagle-import:CJS-1200TB")
      (libsource (lib "eagle-import") (part "CJS-1200TB"))
    )
    (comp (ref "TP10")
      (value "VREF_CASCODE_IBIAS")
      (footprint "eagle-import:KEYSTONE_5000_MINIATURE")
      (libsource (lib "eagle-import") (part "KEYSTONE_5000"))
    )
    (comp (ref "TP11")
      (value "VREF_DIAMOND_IBIAS")
      (footprint "eagle-import:KEYSTONE_5000_MINIATURE")
      (libsource (lib "eagle-import") (part "KEYSTONE_5000"))
    )
    (comp (ref "TP12")
      (value "VREF_ONE_SHOT")
      (footprint "eagle-import:KEYSTONE_5000_MINIATURE")
      (libsource (lib "eagle-import") (part "KEYSTONE_5000"))
    )
    (comp (ref "TP13")
      (value "GND")
      (footprint "eagle-import:KEYSTONE_5000_MINIATURE")
      (libsource (lib "eagle-import") (part "KEYSTONE_5000"))
    )
    (comp (ref "X3")
      (value "CONN_VREF_CASCODE_IBIAS_EXT")
      (footprint "eagle-import:J502-ND-142-0711-871_876")
      (fields (field (name "MF") "JOHNSON COMPONENTS") (field (name "MPN") "142-0711-871"))
      (libsource (lib "eagle-import") (part "SMA-142-0711-871/876"))
    )
    (comp (ref "X4")
      (value "CONN_VREF_DIAMOND_IBIAS_EXT")
      (footprint "eagle-import:J502-ND-142-0711-871_876")
      (fields (field (name "MF") "JOHNSON COMPONENTS") (field (name "MPN") "142-0711-871"))
      (libsource (lib "eagle-import") (part "SMA-142-0711-871/876"))
    )
    (comp (ref "X5")
      (value "CONN_VREF_ONE_SHOT_EXT")
      (footprint "eagle-import:J502-ND-142-0711-871_876")
      (fields (field (name "MF") "JOHNSON COMPONENTS") (field (name "MPN") "142-0711-871"))
      (libsource (lib "eagle-import") (part "SMA-142-0711-871/876"))
    )
  )
  (nets
    (net (code "1") (name "BLANKING_LATCH_EN") (class "Default")
      (node (ref "R29") (pin "1") (pinfunction "1_1") (pintype "passive"))
      (node (ref "R30") (pin "1") (pinfunction "1_1") (pintype "passive"))
      (node (ref "R32") (pin "1") (pinfunction "1_1") (pintype "passive"))
      (node (ref "R34") (pin "1") (pinfunction "1_1") (pintype "passive"))
      (node (ref "R35") (pin "1") (pinfunction "1_1") (pintype "passive"))
      (node (ref "U2") (pin "7") (pinfunction "D0_7") (pintype "input"))
    )
    (net (code "2") (name "COMP_LE_N") (class "Default")
      (node (ref "IC1") (pin "6") (pinfunction "~{LE}_6") (pintype "bidirectional"))
      (node (ref "U2") (pin "1") (pinfunction "Q0_1") (pintype "output"))
    )
    (net (code "3") (name "COMP_LE_P") (class "Default")
      (node (ref "IC1") (pin "7") (pinfunction "LE_7") (pintype "bidirectional"))
      (node (ref "U2") (pin "2") (pinfunction "~{Q0}_2") (pintype "output"))
    )
    (net (code "4") (name "COMP_Q_N") (class "Default")
      (node (ref "IC1") (pin "10") (pinfunction "~{Q}_10") (pintype "bidirectional"))
      (node (ref "R24") (pin "1") (pinfunction "1_1") (pintype "passive"))
      (node (ref "R7") (pin "1") (pinfunction "1_1") (pintype "passive"))
      (node (ref "U1") (pin "3") (pinfunction "~{D}_3") (pintype "input"))
    )
    (net (code "5") (name "COMP_Q_P") (class "Default")
      (node (ref "IC1") (pin "11") (pinfunction "Q_11") (pintype "bidirectional"))
      (node (ref "R24") (pin "2") (pinfunction "2_2") (pintype "passive"))
      (node (ref "R8") (pin "1") (pinfunction "1_1") (pintype "passive"))
      (node (ref "U1") (pin "2") (pinfunction "D_2") (pintype "input"))
    )
    (net (code "6") (name "GND") (class "Default")
      (node (ref "C1") (pin "2") (pinfunction "2_2") (pintype "passive"))
      (node (ref "C10") (pin "2") (pinfunction "2_2") (pintype "passive"))
      (node (ref "C11") (pin "2") (pinfunction "2_2") (pintype "passive"))
      (node (ref "C12") (pin "2") (pinfunction "2_2") (pintype "passive"))
      (node (ref "C13") (pin "2") (pinfunction "2_2") (pintype "passive"))
      (node (ref "C14") (pin "2") (pinfunction "2_2") (pintype "passive"))
      (node (ref "C15") (pin "2") (pinfunction "2_2") (pintype "passive"))
      (node (ref "C16") (pin "2") (pinfunction "2_2") (pintype "passive"))
      (node (ref "C17") (pin "2") (pinfunction "2_2") (pintype "passive"))
      (node (ref "C18") (pin "2") (pinfunction "2_2") (pintype "passive"))
      (node (ref "C19") (pin "2") (pinfunction "2_2") (pintype "passive"))
      (node (ref "C2") (pin "2") (pinfunction "2_2") (pintype "passive"))
      (node (ref "C20") (pin "2") (pinfunction "2_2") (pintype "passive"))
      (node (ref "C21") (pin "2") (pinfunction "2_2") (pintype "passive"))
      (node (ref "C22") (pin "2") (pinfunction "2_2") (pintype "passive"))
      (node (ref "C23") (pin "2") (pinfunction "2_2") (pintype "passive"))
      (node (ref "C24") (pin "2") (pinfunction "2_2") (pintype "passive"))
      (node (ref "C25") (pin "2") (pinfunction "2_2") (pintype "passive"))
      (node (ref "C26") (pin "2") (pinfunction "2_2") (pintype "passive"))
      (node (ref "C27") (pin "2") (pinfunction "2_2") (pintype "passive"))
      (node (ref "C28") (pin "2") (pinfunction "2_2") (pintype "passive"))
      (node (ref "C29") (pin "2") (pinfunction "2_2") (pintype "passive"))
      (node (ref "C3") (pin "2") (pinfunction "2_2") (pintype "passive"))
      (node (ref "C30") (pin "2") (pinfunction "2_2") (pintype "passive"))
      (node (ref "C31") (pin "2") (pinfunction "2_2") (pintype "passive"))
      (node (ref "C32") (pin "2") (pinfunction "2_2") (pintype "passive"))
      (node (ref "C33") (pin "2") (pinfunction "2_2") (pintype "passive"))
      (node (ref "C34") (pin "2") (pinfunction "2_2") (pintype "passive"))
      (node (ref "C35") (pin "2") (pinfunction "2_2") (pintype "passive"))
      (node (ref "C36") (pin "2") (pinfunction "2_2") (pintype "passive"))
      (node (ref "C38") (pin "2") (pinfunction "2_2") (pintype "passive"))
      (node (ref "C39") (pin "2") (pinfunction "2_2") (pintype "passive"))
      (node (ref "C4") (pin "2") (pinfunction "2_2") (pintype "passive"))
      (node (ref "C41") (pin "2") (pinfunction "2_2") (pintype "passive"))
      (node (ref "C42") (pin "2") (pinfunction "2_2") (pintype "passive"))
      (node (ref "C44") (pin "2") (pinfunction "2_2") (pintype "passive"))
      (node (ref "C46") (pin "2") (pinfunction "2_2") (pintype "passive"))
      (node (ref "C47") (pin "2") (pinfunction "2_2") (pintype "passive"))
      (node (ref "C7") (pin "2") (pinfunction "2_2") (pintype "passive"))
      (node (ref "C8") (pin "2") (pinfunction "2_2") (pintype "passive"))
      (node (ref "C9") (pin "-") (pinfunction "-_-") (pintype "passive"))
      (node (ref "H1") (pin "B3,2") (pinfunction "MOUNT_B3,2") (pintype "passive"))
      (node (ref "H2") (pin "B3,2") (pinfunction "MOUNT_B3,2") (pintype "passive"))
      (node (ref "H3") (pin "B3,2") (pinfunction "MOUNT_B3,2") (pintype "passive"))
      (node (ref "H4") (pin "B3,2") (pinfunction "MOUNT_B3,2") (pintype "passive"))
      (node (ref "IC1") (pin "15") (pinfunction "GND_15") (pintype "bidirectional"))
      (node (ref "IC2") (pin "2") (pinfunction "V-_2") (pintype "power_in"))
      (node (ref "IC3") (pin "4") (pinfunction "GND_4") (pintype "bidirectional"))
      (node (ref "IC4") (pin "5") (pinfunction "V+_5") (pintype "power_in"))
      (node (ref "IC5") (pin "2") (pinfunction "GND_2") (pintype "bidirectional"))
      (node (ref "IC6") (pin "4") (pinfunction "V-_4") (pintype "bidirectional"))
      (node (ref "IC6") (pin "5") (pinfunction "LEN_5") (pintype "bidirectional"))
      (node (ref "IC6") (pin "6") (pinfunction "GND_6") (pintype "bidirectional"))
      (node (ref "IC7") (pin "4") (pinfunction "GND_4") (pintype "bidirectional"))
      (node (ref "IC8") (pin "4") (pinfunction "GND_4") (pintype "power_in"))
      (node (ref "IC8") (pin "5") (pinfunction "GND_5") (pintype "power_in"))
      (node (ref "IC9") (pin "4") (pinfunction "GND_4") (pintype "power_in"))
      (node (ref "IC9") (pin "5") (pinfunction "GND_5") (pintype "power_in"))
      (node (ref "J1") (pin "2") (pinfunction "2_2") (pintype "bidirectional"))
      (node (ref "LED2") (pin "C") (pinfunction "C_C") (pintype "passive"))
      (node (ref "M1") (pin "2") (pinfunction "S_2") (pintype "passive"))
      (node (ref "Q4") (pin "C") (pinfunction "C_C") (pintype "passive"))
      (node (ref "Q5") (pin "C") (pinfunction "C_C") (pintype "passive"))
      (node (ref "R1") (pin "1") (pinfunction "1_1") (pintype "passive"))
      (node (ref "R14") (pin "1") (pinfunction "1_1") (pintype "passive"))
      (node (ref "R17") (pin "1") (pinfunction "1_1") (pintype "passive"))
      (node (ref "R2") (pin "2") (pinfunction "2_2") (pintype "passive"))
      (node (ref "R21") (pin "2") (pinfunction "2_2") (pintype "passive"))
      (node (ref "R33") (pin "1") (pinfunction "1_1") (pintype "passive"))
      (node (ref "R36") (pin "2") (pinfunction "2_2") (pintype "passive"))
      (node (ref "R41") (pin "2") (pinfunction "2_2") (pintype "passive"))
      (node (ref "R42") (pin "2") (pinfunction "2_2") (pintype "passive"))
      (node (ref "R43") (pin "2") (pinfunction "2_2") (pintype "passive"))
      (node (ref "R5") (pin "1") (pinfunction "1_1") (pintype "passive"))
      (node (ref "R7") (pin "2") (pinfunction "2_2") (pintype "passive"))
      (node (ref "R8") (pin "2") (pinfunction "2_2") (pintype "passive"))
      (node (ref "RT1") (pin "3") (pinfunction "3_3") (pintype "bidirectional"))
      (node (ref "RT2") (pin "3") (pinfunction "3_3") (pintype "bidirectional"))
      (node (ref "RT3") (pin "3") (pinfunction "3_3") (pintype "bidirectional"))
      (node (ref "RT4") (pin "3") (pinfunction "3_3") (pintype "bidirectional"))
      (node (ref "TP13") (pin "P$1") (pinfunction "P$1_P$1") (pintype "bidirectional"))
      (node (ref "TP3") (pin "P$1") (pinfunction "P$1_P$1") (pintype "bidirectional"))
      (node (ref "TP9") (pin "TP") (pinfunction "TP_TP") (pintype "input"))
      (node (ref "U1") (pin "5") (pinfunction "GND_5") (pintype "passive"))
      (node (ref "U2") (pin "5") (pinfunction "GND_5") (pintype "passive"))
      (node (ref "U2") (pin "6") (pinfunction "D1_6") (pintype "input"))
      (node (ref "U3") (pin "2") (pinfunction "GND_2") (pintype "passive"))
      (node (ref "U3") (pin "4") (pinfunction "GND_2_4") (pintype "passive"))
      (node (ref "X1") (pin "G@1") (pinfunction "GND_G@1") (pintype "power_in"))
      (node (ref "X2") (pin "G@1") (pinfunction "GND_G@1") (pintype "power_in"))
      (node (ref "X3") (pin "G@1") (pinfunction "GND_G@1") (pintype "power_in"))
      (node (ref "X4") (pin "G@1") (pinfunction "GND_G@1") (pintype "power_in"))
      (node (ref "X5") (pin "G@1") (pinfunction "GND_G@1") (pintype "power_in"))
      (node (ref "X6") (pin "G@1") (pinfunction "GND_G@1") (pintype "power_in"))
    )
    (net (code "7") (name "HOLDOFF_TRIG") (class "Default")
      (node (ref "IC3") (pin "1") (pinfunction "CLK_1") (pintype "bidirectional"))
      (node (ref "U1") (pin "7") (pinfunction "Q_7") (pintype "output"))
    )
    (net (code "8") (name "LOGIC_QUENCH") (class "Default")
      (node (ref "IC3") (pin "5") (pinfunction "Q_5") (pintype "bidirectional"))
      (node (ref "IC5") (pin "1") (pinfunction "IN1_1") (pintype "bidirectional"))
      (node (ref "IC5") (pin "3") (pinfunction "IN2_3") (pintype "bidirectional"))
      (node (ref "R20") (pin "2") (pinfunction "2_2") (pintype "passive"))
      (node (ref "R23") (pin "2") (pinfunction "2_2") (pintype "passive"))
    )
    (net (code "9") (name "NC_~{LOGIC_QUENCH}") (class "Default")
      (node (ref "IC3") (pin "3") (pinfunction "~{Q}_3") (pintype "bidirectional"))
      (node (ref "TP1") (pin "TP") (pinfunction "TP_TP") (pintype "input"))
    )
    (net (code "10") (name "Net-(C5-Pad1)") (class "Default")
      (node (ref "C5") (pin "1") (pinfunction "1_1") (pintype "passive"))
      (node (ref "R3") (pin "2") (pinfunction "2_2") (pintype "passive"))
      (node (ref "T1") (pin "E") (pinfunction "E_E") (pintype "passive"))
    )
    (net (code "11") (name "Net-(C5-Pad2)") (class "Default")
      (node (ref "C5") (pin "2") (pinfunction "2_2") (pintype "passive"))
      (node (ref "Q2") (pin "E") (pinfunction "E_E") (pintype "passive"))
      (node (ref "R4") (pin "1") (pinfunction "1_1") (pintype "passive"))
    )
    (net (code "12") (name "Net-(C6-Pad1)") (class "Default")
      (node (ref "C6") (pin "1") (pinfunction "1_1") (pintype "passive"))
      (node (ref "Q1") (pin "C") (pinfunction "C_C") (pintype "passive"))
      (node (ref "R9") (pin "2") (pinfunction "2_2") (pintype "passive"))
      (node (ref "T1") (pin "B") (pinfunction "B_B") (pintype "passive"))
    )
    (net (code "13") (name "Net-(C6-Pad2)") (class "Default")
      (node (ref "C6") (pin "2") (pinfunction "2_2") (pintype "passive"))
      (node (ref "Q2") (pin "B") (pinfunction "B_B") (pintype "passive"))
      (node (ref "R10") (pin "1") (pinfunction "1_1") (pintype "passive"))
      (node (ref "T3") (pin "C") (pinfunction "C_C") (pintype "passive"))
    )
    (net (code "14") (name "Net-(IC1-HYS)") (class "Default")
      (node (ref "IC1") (pin "14") (pinfunction "HYS_14") (pintype "bidirectional"))
      (node (ref "R15") (pin "2") (pinfunction "2_2") (pintype "passive"))
    )
    (net (code "15") (name "Net-(IC1-VTN)") (class "Default")
      (node (ref "IC1") (pin "4") (pinfunction "VTN_4") (pintype "bidirectional"))
      (node (ref "R1") (pin "2") (pinfunction "2_2") (pintype "passive"))
    )
    (net (code "16") (name "Net-(IC1-VTT)") (class "Default")
      (node (ref "IC1") (pin "8") (pinfunction "VTT_8") (pintype "bidirectional"))
      (node (ref "R2") (pin "1") (pinfunction "1_1") (pintype "passive"))
    )
    (net (code "17") (name "Net-(IC2--IN)") (class "Default")
      (node (ref "IC2") (pin "4") (pinfunction "-IN_4") (pintype "input"))
      (node (ref "R17") (pin "2") (pinfunction "2_2") (pintype "passive"))
      (node (ref "T4") (pin "E") (pinfunction "E_E") (pintype "passive"))
    )
    (net (code "18") (name "Net-(IC2-OUT)") (class "Default")
      (node (ref "IC2") (pin "1") (pinfunction "OUT_1") (pintype "output"))
      (node (ref "T3") (pin "B") (pinfunction "B_B") (pintype "passive"))
      (node (ref "T4") (pin "B") (pinfunction "B_B") (pintype "passive"))
    )
    (net (code "19") (name "Net-(IC4--IN)") (class "Default")
      (node (ref "IC4") (pin "4") (pinfunction "-IN_4") (pintype "input"))
      (node (ref "R18") (pin "2") (pinfunction "2_2") (pintype "passive"))
      (node (ref "T6") (pin "E") (pinfunction "E_E") (pintype "passive"))
    )
    (net (code "20") (name "Net-(IC4-OUT)") (class "Default")
      (node (ref "IC4") (pin "1") (pinfunction "OUT_1") (pintype "output"))
      (node (ref "T6") (pin "B") (pinfunction "B_B") (pintype "passive"))
    )
    (net (code "21") (name "Net-(IC5-OUT1)") (class "Default")
      (node (ref "IC5") (pin "4") (pinfunction "OUT2_4") (pintype "bidirectional"))
      (node (ref "IC5") (pin "6") (pinfunction "OUT1_6") (pintype "bidirectional"))
      (node (ref "IC7") (pin "1") (pinfunction "IN_1") (pintype "bidirectional"))
      (node (ref "R28") (pin "2") (pinfunction "2_2") (pintype "passive"))
    )
    (net (code "22") (name "Net-(IC6-+IN)") (class "Default")
      (node (ref "IC6") (pin "2") (pinfunction "+IN_2") (pintype "bidirectional"))
      (node (ref "R25") (pin "1") (pinfunction "1_1") (pintype "passive"))
      (node (ref "R26") (pin "2") (pinfunction "2_2") (pintype "passive"))
    )
    (net (code "23") (name "Net-(IC7-TAP1)") (class "Default")
      (node (ref "IC7") (pin "7") (pinfunction "TAP1_7") (pintype "bidirectional"))
      (node (ref "R35") (pin "2") (pinfunction "2_2") (pintype "passive"))
    )
    (net (code "24") (name "Net-(IC7-TAP2)") (class "Default")
      (node (ref "IC7") (pin "2") (pinfunction "TAP2_2") (pintype "bidirectional"))
      (node (ref "R29") (pin "2") (pinfunction "2_2") (pintype "passive"))
    )
    (net (code "25") (name "Net-(IC7-TAP3)") (class "Default")
      (node (ref "IC7") (pin "6") (pinfunction "TAP3_6") (pintype "bidirectional"))
      (node (ref "R32") (pin "2") (pinfunction "2_2") (pintype "passive"))
    )
    (net (code "26") (name "Net-(IC7-TAP4)") (class "Default")
      (node (ref "IC7") (pin "3") (pinfunction "TAP4_3") (pintype "bidirectional"))
      (node (ref "R30") (pin "2") (pinfunction "2_2") (pintype "passive"))
    )
    (net (code "27") (name "Net-(IC7-TAP5)") (class "Default")
      (node (ref "IC7") (pin "5") (pinfunction "TAP5_5") (pintype "bidirectional"))
      (node (ref "R34") (pin "2") (pinfunction "2_2") (pintype "passive"))
    )
    (net (code "28") (name "Net-(IC8-BN)") (class "Default")
      (node (ref "C40") (pin "1") (pinfunction "1_1") (pintype "passive"))
      (node (ref "IC8") (pin "11") (pinfunction "BN_11") (pintype "bidirectional"))
    )
    (net (code "29") (name "Net-(IC8-BP)") (class "Default")
      (node (ref "C37") (pin "1") (pinfunction "1_1") (pintype "passive"))
      (node (ref "IC8") (pin "3") (pinfunction "BP_3") (pintype "bidirectional"))
    )
    (net (code "30") (name "Net-(IC9-BN)") (class "Default")
      (node (ref "C45") (pin "1") (pinfunction "1_1") (pintype "passive"))
      (node (ref "IC9") (pin "11") (pinfunction "BN_11") (pintype "bidirectional"))
    )
    (net (code "31") (name "Net-(IC9-BP)") (class "Default")
      (node (ref "C43") (pin "1") (pinfunction "1_1") (pintype "passive"))
      (node (ref "IC9") (pin "3") (pinfunction "BP_3") (pintype "bidirectional"))
    )
    (net (code "32") (name "Net-(LED1-PadA)") (class "Default")
      (node (ref "LED1") (pin "A") (pinfunction "A_A") (pintype "passive"))
      (node (ref "R36") (pin "1") (pinfunction "1_1") (pintype "passive"))
    )
    (net (code "33") (name "Net-(LED2-PadA)") (class "Default")
      (node (ref "LED2") (pin "A") (pinfunction "A_A") (pintype "passive"))
      (node (ref "R37") (pin "1") (pinfunction "1_1") (pintype "passive"))
    )
    (net (code "34") (name "Net-(M1-G)") (class "Default")
      (node (ref "D1") (pin "C") (pinfunction "C_C") (pintype "passive"))
      (node (ref "M1") (pin "1") (pinfunction "G_1") (pintype "passive"))
      (node (ref "R27") (pin "2") (pinfunction "2_2") (pintype "passive"))
    )
    (net (code "35") (name "Net-(Q1-PadB)") (class "Default")
      (node (ref "Q1") (pin "B") (pinfunction "B_B") (pintype "passive"))
      (node (ref "Q4") (pin "E") (pinfunction "E_E") (pintype "passive"))
      (node (ref "Q6") (pin "B") (pinfunction "B_B") (pintype "passive"))
    )
    (net (code "36") (name "Net-(Q1-PadE)") (class "Default")
      (node (ref "Q1") (pin "E") (pinfunction "E_E") (pintype "passive"))
      (node (ref "R6") (pin "1") (pinfunction "1_1") (pintype "passive"))
    )
    (net (code "37") (name "Net-(Q2-PadC)") (class "Default")
      (node (ref "Q2") (pin "C") (pinfunction "C_C") (pintype "passive"))
      (node (ref "Q3") (pin "E") (pinfunction "E_E") (pintype "passive"))
    )
    (net (code "38") (name "Net-(Q4-PadB)") (class "Default")
      (node (ref "Q4") (pin "B") (pinfunction "B_B") (pintype "passive"))
      (node (ref "Q6") (pin "C") (pinfunction "C_C") (pintype "passive"))
      (node (ref "R11") (pin "2") (pinfunction "2_2") (pintype "passive"))
    )
    (net (code "39") (name "Net-(Q5-PadB)") (class "Default")
      (node (ref "Q5") (pin "B") (pinfunction "B_B") (pintype "passive"))
      (node (ref "R13") (pin "1") (pinfunction "1_1") (pintype "passive"))
      (node (ref "T2") (pin "B") (pinfunction "B_B") (pintype "passive"))
    )
    (net (code "40") (name "Net-(Q5-PadE)") (class "Default")
      (node (ref "Q5") (pin "E") (pinfunction "E_E") (pintype "passive"))
      (node (ref "R9") (pin "1") (pinfunction "1_1") (pintype "passive"))
    )
    (net (code "41") (name "Net-(Q6-PadE)") (class "Default")
      (node (ref "Q6") (pin "E") (pinfunction "E_E") (pintype "passive"))
      (node (ref "R16") (pin "1") (pinfunction "1_1") (pintype "passive"))
    )
    (net (code "42") (name "Net-(R10-Pad2)") (class "Default")
      (node (ref "R10") (pin "2") (pinfunction "2_2") (pintype "passive"))
      (node (ref "T2") (pin "E") (pinfunction "E_E") (pintype "passive"))
    )
    (net (code "43") (name "Net-(R11-Pad1)") (class "Default")
      (node (ref "R11") (pin "1") (pinfunction "1_1") (pintype "passive"))
      (node (ref "T4") (pin "C") (pinfunction "C_C") (pintype "passive"))
    )
    (net (code "44") (name "Net-(R12-Pad1)") (class "Default")
      (node (ref "R12") (pin "1") (pinfunction "1_1") (pintype "passive"))
      (node (ref "R13") (pin "2") (pinfunction "2_2") (pintype "passive"))
      (node (ref "T5") (pin "C") (pinfunction "C_C") (pintype "passive"))
    )
    (net (code "45") (name "Net-(R14-Pad2)") (class "Default")
      (node (ref "R14") (pin "2") (pinfunction "2_2") (pintype "passive"))
      (node (ref "T3") (pin "E") (pinfunction "E_E") (pintype "passive"))
    )
    (net (code "46") (name "Net-(R19-Pad2)") (class "Default")
      (node (ref "R19") (pin "2") (pinfunction "2_2") (pintype "passive"))
      (node (ref "T6") (pin "C") (pinfunction "C_C") (pintype "passive"))
      (node (ref "T7") (pin "E") (pinfunction "E_E") (pintype "passive"))
    )
    (net (code "47") (name "Net-(R20-Pad1)") (class "Default")
      (node (ref "R20") (pin "1") (pinfunction "1_1") (pintype "passive"))
      (node (ref "R21") (pin "1") (pinfunction "1_1") (pintype "passive"))
      (node (ref "T7") (pin "B") (pinfunction "B_B") (pintype "passive"))
    )
    (net (code "48") (name "Net-(R28-Pad1)") (class "Default")
      (node (ref "R28") (pin "1") (pinfunction "1_1") (pintype "passive"))
      (node (ref "X2") (pin "1") (pinfunction "1_1") (pintype "passive"))
    )
    (net (code "49") (name "Net-(T5-PadE)") (class "Default")
      (node (ref "T5") (pin "E") (pinfunction "E_E") (pintype "passive"))
      (node (ref "T7") (pin "C") (pinfunction "C_C") (pintype "passive"))
    )
    (net (code "50") (name "ONE_SHOT_CAP") (class "Default")
      (node (ref "C23") (pin "1") (pinfunction "1_1") (pintype "passive"))
      (node (ref "M1") (pin "3") (pinfunction "D_3") (pintype "passive"))
      (node (ref "R23") (pin "1") (pinfunction "1_1") (pintype "passive"))
      (node (ref "R25") (pin "2") (pinfunction "2_2") (pintype "passive"))
    )
    (net (code "51") (name "ONE_SHOT_CLR") (class "Default")
      (node (ref "D1") (pin "A") (pinfunction "A_A") (pintype "passive"))
      (node (ref "IC6") (pin "7") (pinfunction "Q_7") (pintype "bidirectional"))
      (node (ref "R26") (pin "1") (pinfunction "1_1") (pintype "passive"))
      (node (ref "R27") (pin "1") (pinfunction "1_1") (pintype "passive"))
    )
    (net (code "52") (name "PP_N5V0") (class "Default")
      (node (ref "C12") (pin "1") (pinfunction "1_1") (pintype "passive"))
      (node (ref "C13") (pin "1") (pinfunction "1_1") (pintype "passive"))
      (node (ref "C25") (pin "1") (pinfunction "1_1") (pintype "passive"))
      (node (ref "C28") (pin "1") (pinfunction "1_1") (pintype "passive"))
      (node (ref "C40") (pin "2") (pinfunction "2_2") (pintype "passive"))
      (node (ref "C41") (pin "1") (pinfunction "1_1") (pintype "passive"))
      (node (ref "IC1") (pin "13") (pinfunction "VEE_13") (pintype "bidirectional"))
      (node (ref "IC4") (pin "2") (pinfunction "V-_2") (pintype "power_in"))
      (node (ref "IC8") (pin "7") (pinfunction "ON_7") (pintype "power_in"))
      (node (ref "LED1") (pin "C") (pinfunction "C_C") (pintype "passive"))
      (node (ref "R15") (pin "1") (pinfunction "1_1") (pintype "passive"))
      (node (ref "R18") (pin "1") (pinfunction "1_1") (pintype "passive"))
      (node (ref "R19") (pin "1") (pinfunction "1_1") (pintype "passive"))
      (node (ref "R38") (pin "1") (pinfunction "1_1") (pintype "passive"))
      (node (ref "RT2") (pin "1") (pinfunction "1_1") (pintype "bidirectional"))
      (node (ref "TP5") (pin "TP") (pinfunction "TP_TP") (pintype "input"))
    )
    (net (code "53") (name "PP_N15V0") (class "Default")
      (node (ref "C45") (pin "2") (pinfunction "2_2") (pintype "passive"))
      (node (ref "C47") (pin "1") (pinfunction "1_1") (pintype "passive"))
      (node (ref "IC8") (pin "6") (pinfunction "IN_6") (pintype "power_in"))
      (node (ref "IC8") (pin "9") (pinfunction "IN_9") (pintype "power_in"))
      (node (ref "IC9") (pin "7") (pinfunction "ON_7") (pintype "power_in"))
      (node (ref "TP7") (pin "TP") (pinfunction "TP_TP") (pintype "input"))
    )
    (net (code "54") (name "PP_NVIN") (class "Default")
      (node (ref "C46") (pin "1") (pinfunction "1_1") (pintype "passive"))
      (node (ref "IC9") (pin "6") (pinfunction "IN_6") (pintype "power_in"))
      (node (ref "IC9") (pin "9") (pinfunction "IN_9") (pintype "power_in"))
      (node (ref "J1") (pin "3") (pinfunction "3_3") (pintype "bidirectional"))
    )
    (net (code "55") (name "PP_P3V3") (class "Default")
      (node (ref "C16") (pin "1") (pinfunction "1_1") (pintype "passive"))
      (node (ref "C19") (pin "1") (pinfunction "1_1") (pintype "passive"))
      (node (ref "C21") (pin "1") (pinfunction "1_1") (pintype "passive"))
      (node (ref "C22") (pin "1") (pinfunction "1_1") (pintype "passive"))
      (node (ref "C24") (pin "1") (pinfunction "1_1") (pintype "passive"))
      (node (ref "C27") (pin "1") (pinfunction "1_1") (pintype "passive"))
      (node (ref "C30") (pin "1") (pinfunction "1_1") (pintype "passive"))
      (node (ref "C31") (pin "1") (pinfunction "1_1") (pintype "passive"))
      (node (ref "C32") (pin "1") (pinfunction "1_1") (pintype "passive"))
      (node (ref "C33") (pin "1") (pinfunction "1_1") (pintype "passive"))
      (node (ref "C34") (pin "1") (pinfunction "1_1") (pintype "passive"))
      (node (ref "C35") (pin "1") (pinfunction "1_1") (pintype "passive"))
      (node (ref "C4") (pin "1") (pinfunction "1_1") (pintype "passive"))
      (node (ref "C42") (pin "1") (pinfunction "1_1") (pintype "passive"))
      (node (ref "C8") (pin "1") (pinfunction "1_1") (pintype "passive"))
      (node (ref "IC1") (pin "12") (pinfunction "VCCO_12") (pintype "bidirectional"))
      (node (ref "IC1") (pin "9") (pinfunction "VCCO_9") (pintype "bidirectional"))
      (node (ref "IC3") (pin "2") (pinfunction "D_2") (pintype "bidirectional"))
      (node (ref "IC3") (pin "8") (pinfunction "VDD_8") (pintype "bidirectional"))
      (node (ref "IC5") (pin "5") (pinfunction "VCC_5") (pintype "bidirectional"))
      (node (ref "IC6") (pin "1") (pinfunction "V+_1") (pintype "bidirectional"))
      (node (ref "IC7") (pin "8") (pinfunction "VCC_8") (pintype "bidirectional"))
      (node (ref "R22") (pin "2") (pinfunction "2_2") (pintype "passive"))
      (node (ref "R40") (pin "1") (pinfunction "1_1") (pintype "passive"))
      (node (ref "RT4") (pin "1") (pinfunction "1_1") (pintype "bidirectional"))
      (node (ref "TP4") (pin "TP") (pinfunction "TP_TP") (pintype "input"))
      (node (ref "U1") (pin "8") (pinfunction "VCC_8") (pintype "power_in"))
      (node (ref "U2") (pin "8") (pinfunction "VCC_8") (pintype "power_in"))
      (node (ref "U3") (pin "5") (pinfunction "OUT_5") (pintype "output"))
    )
    (net (code "56") (name "PP_P5V0") (class "Default")
      (node (ref "C11") (pin "1") (pinfunction "1_1") (pintype "passive"))
      (node (ref "C15") (pin "1") (pinfunction "1_1") (pintype "passive"))
      (node (ref "C17") (pin "1") (pinfunction "1_1") (pintype "passive"))
      (node (ref "C2") (pin "1") (pinfunction "1_1") (pintype "passive"))
      (node (ref "C20") (pin "1") (pinfunction "1_1") (pintype "passive"))
      (node (ref "C36") (pin "1") (pinfunction "1_1") (pintype "passive"))
      (node (ref "C37") (pin "2") (pinfunction "2_2") (pintype "passive"))
      (node (ref "C39") (pin "1") (pinfunction "1_1") (pintype "passive"))
      (node (ref "C7") (pin "1") (pinfunction "1_1") (pintype "passive"))
      (node (ref "IC1") (pin "16") (pinfunction "VCCI_16") (pintype "bidirectional"))
      (node (ref "IC1") (pin "5") (pinfunction "VCCI_5") (pintype "bidirectional"))
      (node (ref "IC2") (pin "5") (pinfunction "V+_5") (pintype "power_in"))
      (node (ref "IC8") (pin "1") (pinfunction "OP_1") (pintype "power_in"))
      (node (ref "Q3") (pin "B") (pinfunction "B_B") (pintype "passive"))
      (node (ref "R31") (pin "2") (pinfunction "2_2") (pintype "passive"))
      (node (ref "R37") (pin "2") (pinfunction "2_2") (pintype "passive"))
      (node (ref "R39") (pin "1") (pinfunction "1_1") (pintype "passive"))
      (node (ref "RT1") (pin "1") (pinfunction "1_1") (pintype "bidirectional"))
      (node (ref "RT3") (pin "1") (pinfunction "1_1") (pintype "bidirectional"))
      (node (ref "T5") (pin "B") (pinfunction "B_B") (pintype "passive"))
      (node (ref "TP6") (pin "TP") (pinfunction "TP_TP") (pintype "input"))
      (node (ref "U3") (pin "1") (pinfunction "IN_1") (pintype "input"))
      (node (ref "U3") (pin "3") (pinfunction "EN_3") (pintype "input"))
    )
    (net (code "57") (name "PP_P15V0") (class "Default")
      (node (ref "C1") (pin "1") (pinfunction "1_1") (pintype "passive"))
      (node (ref "C14") (pin "1") (pinfunction "1_1") (pintype "passive"))
      (node (ref "C3") (pin "1") (pinfunction "1_1") (pintype "passive"))
      (node (ref "C38") (pin "1") (pinfunction "1_1") (pintype "passive"))
      (node (ref "C43") (pin "2") (pinfunction "2_2") (pintype "passive"))
      (node (ref "C9") (pin "+") (pinfunction "+_+") (pintype "passive"))
      (node (ref "IC8") (pin "10") (pinfunction "~{SN}_10") (pintype "bidirectional"))
      (node (ref "IC8") (pin "12") (pinfunction "~{SP}_12") (pintype "bidirectional"))
      (node (ref "IC8") (pin "14") (pinfunction "IP_14") (pintype "power_in"))
      (node (ref "IC9") (pin "1") (pinfunction "OP_1") (pintype "power_in"))
      (node (ref "R12") (pin "2") (pinfunction "2_2") (pintype "passive"))
      (node (ref "R16") (pin "2") (pinfunction "2_2") (pintype "passive"))
      (node (ref "R6") (pin "2") (pinfunction "2_2") (pintype "passive"))
      (node (ref "T1") (pin "C") (pinfunction "C_C") (pintype "passive"))
      (node (ref "T2") (pin "C") (pinfunction "C_C") (pintype "passive"))
      (node (ref "TP8") (pin "TP") (pinfunction "TP_TP") (pintype "input"))
    )
    (net (code "58") (name "PP_PVIN") (class "Default")
      (node (ref "C44") (pin "1") (pinfunction "1_1") (pintype "passive"))
      (node (ref "IC9") (pin "10") (pinfunction "~{SN}_10") (pintype "bidirectional"))
      (node (ref "IC9") (pin "12") (pinfunction "~{SP}_12") (pintype "bidirectional"))
      (node (ref "IC9") (pin "14") (pinfunction "IP_14") (pintype "power_in"))
      (node (ref "J1") (pin "1") (pinfunction "1_1") (pintype "bidirectional"))
    )
    (net (code "59") (name "SPAD_PULLDN_SENSE") (class "Default")
      (node (ref "IC1") (pin "3") (pinfunction "VN_3") (pintype "bidirectional"))
      (node (ref "Q3") (pin "C") (pinfunction "C_C") (pintype "passive"))
      (node (ref "R5") (pin "2") (pinfunction "2_2") (pintype "passive"))
    )
    (net (code "60") (name "VBB") (class "Default")
      (node (ref "U1") (pin "4") (pinfunction "VBB_4") (pintype "power_in"))
    )
    (net (code "61") (name "VREF_AV_DET") (class "Default")
      (node (ref "C10") (pin "1") (pinfunction "1_1") (pintype "passive"))
      (node (ref "IC1") (pin "2") (pinfunction "VP_2") (pintype "bidirectional"))
      (node (ref "R31") (pin "1") (pinfunction "1_1") (pintype "passive"))
      (node (ref "R33") (pin "2") (pinfunction "2_2") (pintype "passive"))
      (node (ref "RT1") (pin "2") (pinfunction "2_2") (pintype "bidirectional"))
      (node (ref "TP2") (pin "P$1") (pinfunction "P$1_P$1") (pintype "bidirectional"))
    )
    (net (code "62") (name "VREF_CASCODE_IBIAS") (class "Default")
      (node (ref "C26") (pin "1") (pinfunction "1_1") (pintype "passive"))
      (node (ref "IC4") (pin "3") (pinfunction "+IN_3") (pintype "input"))
      (node (ref "SW1") (pin "2") (pinfunction "COM_2") (pintype "bidirectional"))
      (node (ref "TP10") (pin "P$1") (pinfunction "P$1_P$1") (pintype "bidirectional"))
    )
    (net (code "63") (name "VREF_CASCODE_IBIAS_EXT") (class "Default")
      (node (ref "SW1") (pin "1") (pinfunction "NO_1") (pintype "bidirectional"))
      (node (ref "X3") (pin "1") (pinfunction "1_1") (pintype "passive"))
    )
    (net (code "64") (name "VREF_CASCODE_IBIAS_INT") (class "Default")
      (node (ref "R38") (pin "2") (pinfunction "2_2") (pintype "passive"))
      (node (ref "R41") (pin "1") (pinfunction "1_1") (pintype "passive"))
      (node (ref "RT2") (pin "2") (pinfunction "2_2") (pintype "bidirectional"))
      (node (ref "SW1") (pin "3") (pinfunction "NC_3") (pintype "bidirectional"))
    )
    (net (code "65") (name "VREF_DIAMOND_IBIAS") (class "Default")
      (node (ref "C18") (pin "1") (pinfunction "1_1") (pintype "passive"))
      (node (ref "IC2") (pin "3") (pinfunction "+IN_3") (pintype "input"))
      (node (ref "SW2") (pin "2") (pinfunction "COM_2") (pintype "bidirectional"))
      (node (ref "TP11") (pin "P$1") (pinfunction "P$1_P$1") (pintype "bidirectional"))
    )
    (net (code "66") (name "VREF_DIAMOND_IBIAS_EXT") (class "Default")
      (node (ref "SW2") (pin "1") (pinfunction "NO_1") (pintype "bidirectional"))
      (node (ref "X4") (pin "1") (pinfunction "1_1") (pintype "passive"))
    )
    (net (code "67") (name "VREF_DIAMOND_IBIAS_INT") (class "Default")
      (node (ref "R39") (pin "2") (pinfunction "2_2") (pintype "passive"))
      (node (ref "R42") (pin "1") (pinfunction "1_1") (pintype "passive"))
      (node (ref "RT3") (pin "2") (pinfunction "2_2") (pintype "bidirectional"))
      (node (ref "SW2") (pin "3") (pinfunction "NC_3") (pintype "bidirectional"))
    )
    (net (code "68") (name "VREF_ONE_SHOT") (class "Default")
      (node (ref "C29") (pin "1") (pinfunction "1_1") (pintype "passive"))
      (node (ref "IC6") (pin "3") (pinfunction "-IN_3") (pintype "bidirectional"))
      (node (ref "SW3") (pin "2") (pinfunction "COM_2") (pintype "bidirectional"))
      (node (ref "TP12") (pin "P$1") (pinfunction "P$1_P$1") (pintype "bidirectional"))
    )
    (net (code "69") (name "VREF_ONE_SHOT_EXT") (class "Default")
      (node (ref "SW3") (pin "1") (pinfunction "NO_1") (pintype "bidirectional"))
      (node (ref "X5") (pin "1") (pinfunction "1_1") (pintype "passive"))
    )
    (net (code "70") (name "VREF_ONE_SHOT_INT") (class "Default")
      (node (ref "R40") (pin "2") (pinfunction "2_2") (pintype "passive"))
      (node (ref "R43") (pin "1") (pinfunction "1_1") (pintype "passive"))
      (node (ref "RT4") (pin "2") (pinfunction "2_2") (pintype "bidirectional"))
      (node (ref "SW3") (pin "3") (pinfunction "NC_3") (pintype "bidirectional"))
    )
    (net (code "71") (name "VSPAD") (class "Default")
      (node (ref "R3") (pin "1") (pinfunction "1_1") (pintype "passive"))
      (node (ref "R4") (pin "2") (pinfunction "2_2") (pintype "passive"))
      (node (ref "X1") (pin "1") (pinfunction "1_1") (pintype "passive"))
    )
    (net (code "72") (name "unconnected-(IC1-VTP-Pad1)") (class "Default")
      (node (ref "IC1") (pin "1") (pinfunction "VTP_1") (pintype "bidirectional"))
    )
    (net (code "73") (name "unconnected-(IC8-AJN-Pad8)") (class "Default")
      (node (ref "IC8") (pin "8") (pinfunction "AJN_8") (pintype "bidirectional"))
    )
    (net (code "74") (name "unconnected-(IC8-AJP-Pad2)") (class "Default")
      (node (ref "IC8") (pin "2") (pinfunction "AJP_2") (pintype "bidirectional"))
    )
    (net (code "75") (name "unconnected-(IC9-AJN-Pad8)") (class "Default")
      (node (ref "IC9") (pin "8") (pinfunction "AJN_8") (pintype "bidirectional"))
    )
    (net (code "76") (name "unconnected-(IC9-AJP-Pad2)") (class "Default")
      (node (ref "IC9") (pin "2") (pinfunction "AJP_2") (pintype "bidirectional"))
    )
    (net (code "77") (name "unconnected-(U1-NC-Pad6)") (class "Default")
      (node (ref "U1") (pin "6") (pinfunction "NC_6") (pintype "no_connect"))
    )
    (net (code "78") (name "unconnected-(U1-NC_2-Pad1)") (class "Default")
      (node (ref "U1") (pin "1") (pinfunction "NC_2_1") (pintype "no_connect"))
    )
    (net (code "79") (name "unconnected-(U2-Q1-Pad3)") (class "Default")
      (node (ref "U2") (pin "3") (pinfunction "Q1_3") (pintype "output"))
    )
    (net (code "80") (name "unconnected-(U2-~{Q1}-Pad4)") (class "Default")
      (node (ref "U2") (pin "4") (pinfunction "~{Q1}_4") (pintype "output"))
    )
    (net (code "81") (name "~{FORCE_QUENCH}") (class "Default")
      (node (ref "IC3") (pin "7") (pinfunction "~{PRE}_7") (pintype "bidirectional"))
      (node (ref "R22") (pin "1") (pinfunction "1_1") (pintype "passive"))
      (node (ref "X6") (pin "1") (pinfunction "1_1") (pintype "passive"))
    )
    (net (code "82") (name "~{ONE_SHOT_CLR}") (class "Default")
      (node (ref "IC3") (pin "6") (pinfunction "~{CLR}_6") (pintype "bidirectional"))
      (node (ref "IC6") (pin "8") (pinfunction "~{Q}_8") (pintype "bidirectional"))
    )
  )
)
